# thermocouple_1.net
KiCad netlist of a schematic drawn in Altium Designer
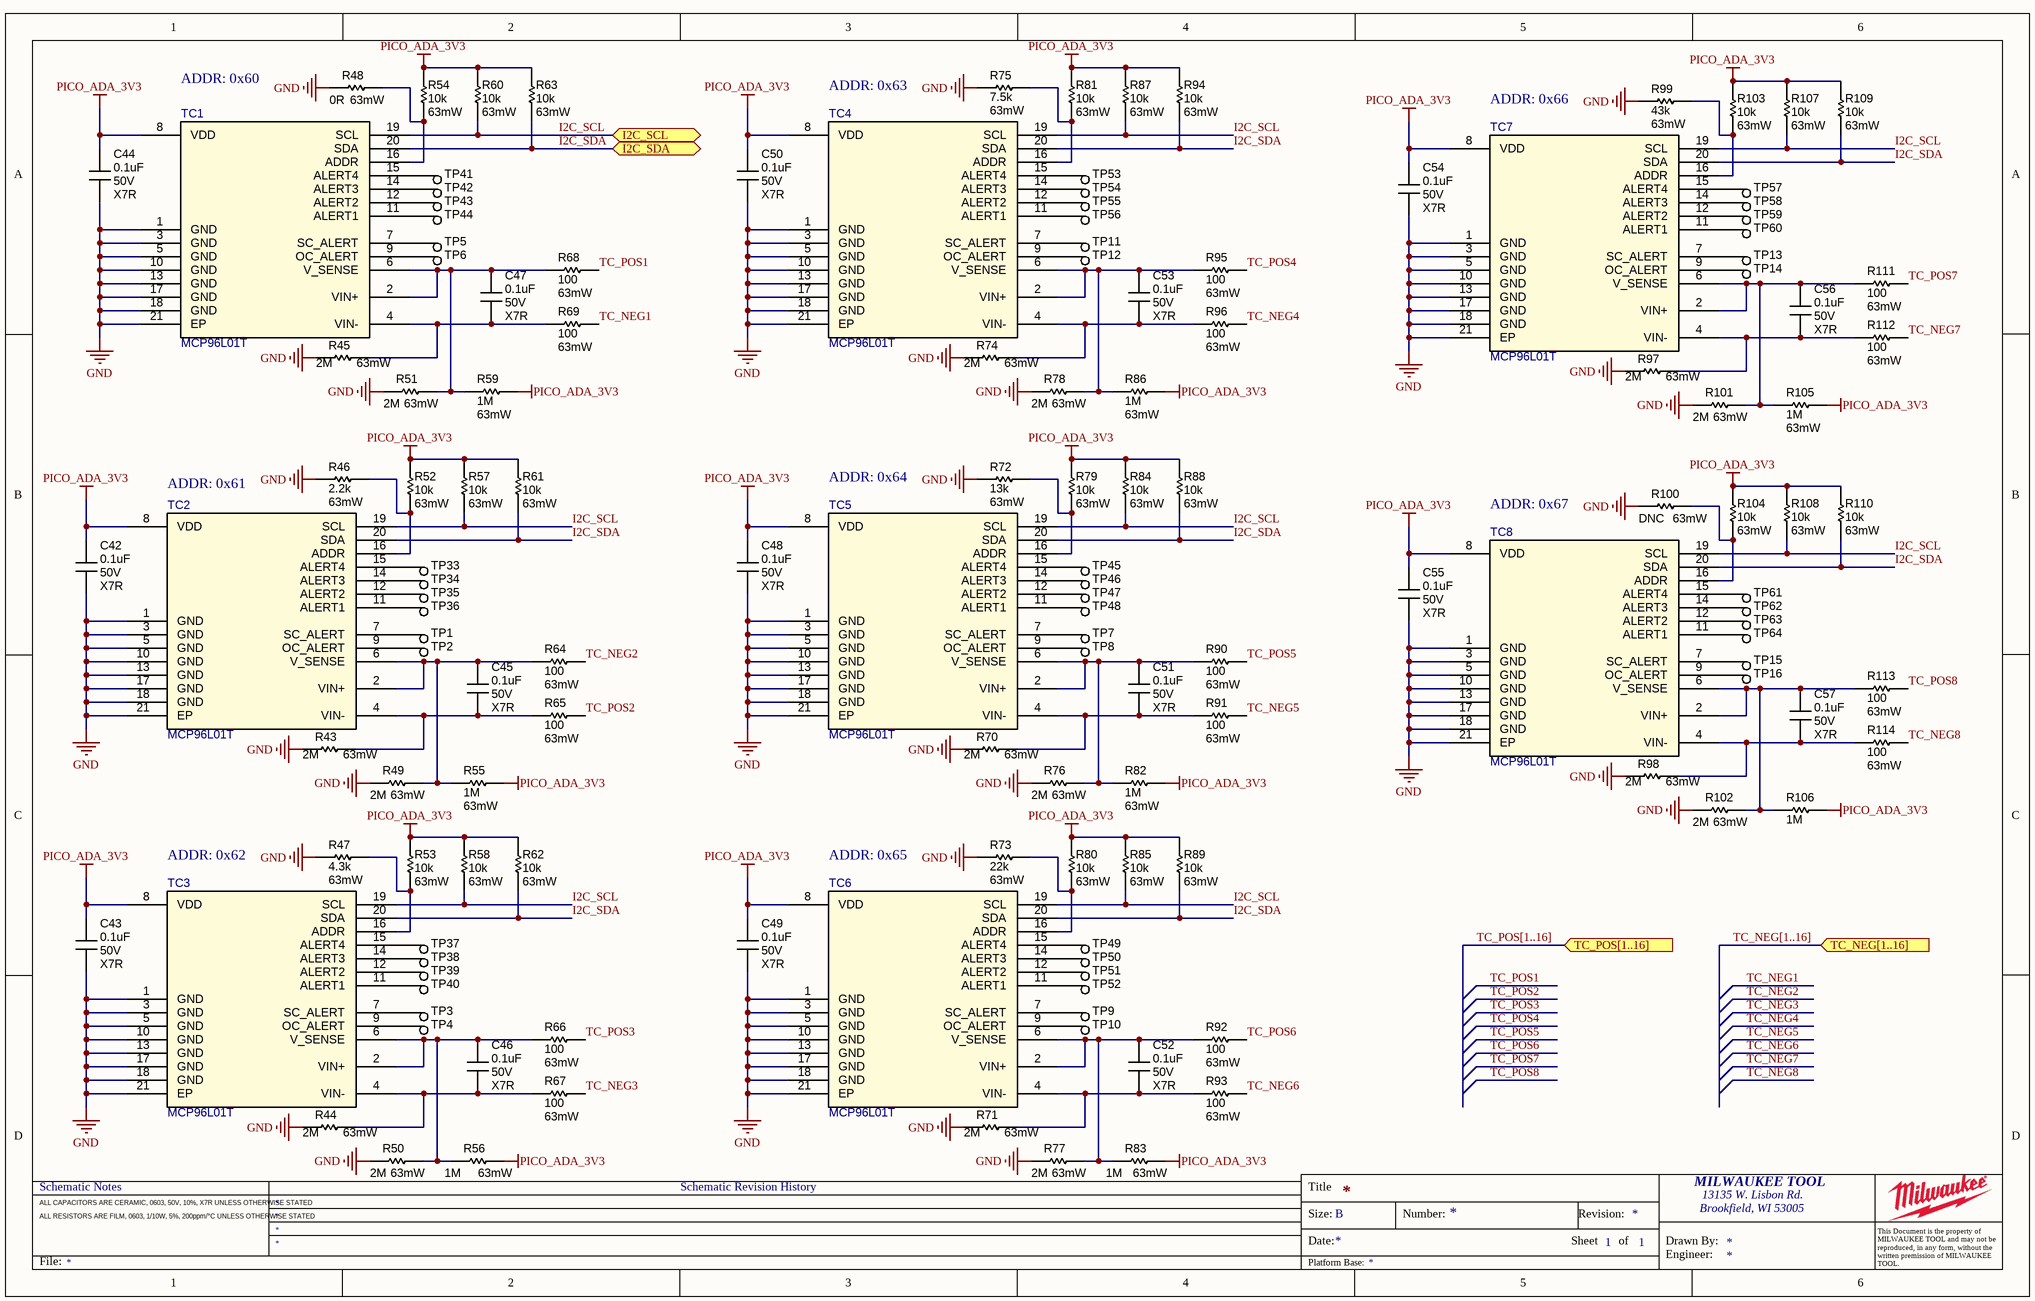
[diagram p0: thermocouple_1.SchDoc]

(export (version "E")
  (design (tool "Eeschema 10.0.6"))
  (components
    (comp (ref "C42")
      (value "0.1uF")
      (footprint "CAPC1608X09N")
      (description "CAP CER 0.1UF 50V X7R 0603")
      (fields
        (field (name "TOLERANCE") "10%")
        (field (name "MFR") "KEMET")
        (field (name "VOLTAGE RATING") "50V")
        (field (name "TEMP COEFF") "X7R")
      )
      (libsource (lib "General_Library") (part "CMP-004-0070"))
    )
    (comp (ref "C43")
      (value "0.1uF")
      (footprint "CAPC1608X09N")
      (description "CAP CER 0.1UF 50V X7R 0603")
      (fields
        (field (name "TOLERANCE") "10%")
        (field (name "MFR") "KEMET")
        (field (name "VOLTAGE RATING") "50V")
        (field (name "TEMP COEFF") "X7R")
      )
      (libsource (lib "General_Library") (part "CMP-004-0070"))
    )
    (comp (ref "C44")
      (value "0.1uF")
      (footprint "CAPC1608X09N")
      (description "CAP CER 0.1UF 50V X7R 0603")
      (fields
        (field (name "TOLERANCE") "10%")
        (field (name "MFR") "KEMET")
        (field (name "VOLTAGE RATING") "50V")
        (field (name "TEMP COEFF") "X7R")
      )
      (libsource (lib "General_Library") (part "CMP-004-0070"))
    )
    (comp (ref "C45")
      (value "0.1uF")
      (footprint "CAPC1005X06N")
      (description "CAP CER SMD 0.1UF 50V X7R 0402")
      (fields
        (field (name "TOLERANCE") "10%")
        (field (name "MFR") "Murata Electronics")
        (field (name "VOLTAGE RATING") "50V")
        (field (name "TEMP COEFF") "X7R")
      )
      (libsource (lib "General_Library") (part "CMP-004-0076"))
    )
    (comp (ref "C46")
      (value "0.1uF")
      (footprint "CAPC1005X06N")
      (description "CAP CER SMD 0.1UF 50V X7R 0402")
      (fields
        (field (name "TOLERANCE") "10%")
        (field (name "MFR") "Murata Electronics")
        (field (name "VOLTAGE RATING") "50V")
        (field (name "TEMP COEFF") "X7R")
      )
      (libsource (lib "General_Library") (part "CMP-004-0076"))
    )
    (comp (ref "C47")
      (value "0.1uF")
      (footprint "CAPC1005X06N")
      (description "CAP CER SMD 0.1UF 50V X7R 0402")
      (fields
        (field (name "TOLERANCE") "10%")
        (field (name "MFR") "Murata Electronics")
        (field (name "VOLTAGE RATING") "50V")
        (field (name "TEMP COEFF") "X7R")
      )
      (libsource (lib "General_Library") (part "CMP-004-0076"))
    )
    (comp (ref "C48")
      (value "0.1uF")
      (footprint "CAPC1608X09N")
      (description "CAP CER 0.1UF 50V X7R 0603")
      (fields
        (field (name "TOLERANCE") "10%")
        (field (name "MFR") "KEMET")
        (field (name "VOLTAGE RATING") "50V")
        (field (name "TEMP COEFF") "X7R")
      )
      (libsource (lib "General_Library") (part "CMP-004-0070"))
    )
    (comp (ref "C49")
      (value "0.1uF")
      (footprint "CAPC1608X09N")
      (description "CAP CER 0.1UF 50V X7R 0603")
      (fields
        (field (name "TOLERANCE") "10%")
        (field (name "MFR") "KEMET")
        (field (name "VOLTAGE RATING") "50V")
        (field (name "TEMP COEFF") "X7R")
      )
      (libsource (lib "General_Library") (part "CMP-004-0070"))
    )
    (comp (ref "C50")
      (value "0.1uF")
      (footprint "CAPC1608X09N")
      (description "CAP CER 0.1UF 50V X7R 0603")
      (fields
        (field (name "TOLERANCE") "10%")
        (field (name "MFR") "KEMET")
        (field (name "VOLTAGE RATING") "50V")
        (field (name "TEMP COEFF") "X7R")
      )
      (libsource (lib "General_Library") (part "CMP-004-0070"))
    )
    (comp (ref "C51")
      (value "0.1uF")
      (footprint "CAPC1005X06N")
      (description "CAP CER SMD 0.1UF 50V X7R 0402")
      (fields
        (field (name "TOLERANCE") "10%")
        (field (name "MFR") "Murata Electronics")
        (field (name "VOLTAGE RATING") "50V")
        (field (name "TEMP COEFF") "X7R")
      )
      (libsource (lib "General_Library") (part "CMP-004-0076"))
    )
    (comp (ref "C52")
      (value "0.1uF")
      (footprint "CAPC1005X06N")
      (description "CAP CER SMD 0.1UF 50V X7R 0402")
      (fields
        (field (name "TOLERANCE") "10%")
        (field (name "MFR") "Murata Electronics")
        (field (name "VOLTAGE RATING") "50V")
        (field (name "TEMP COEFF") "X7R")
      )
      (libsource (lib "General_Library") (part "CMP-004-0076"))
    )
    (comp (ref "C53")
      (value "0.1uF")
      (footprint "CAPC1005X06N")
      (description "CAP CER SMD 0.1UF 50V X7R 0402")
      (fields
        (field (name "TOLERANCE") "10%")
        (field (name "MFR") "Murata Electronics")
        (field (name "VOLTAGE RATING") "50V")
        (field (name "TEMP COEFF") "X7R")
      )
      (libsource (lib "General_Library") (part "CMP-004-0076"))
    )
    (comp (ref "C54")
      (value "0.1uF")
      (footprint "CAPC1608X09N")
      (description "CAP CER 0.1UF 50V X7R 0603")
      (fields
        (field (name "TOLERANCE") "10%")
        (field (name "MFR") "KEMET")
        (field (name "VOLTAGE RATING") "50V")
        (field (name "TEMP COEFF") "X7R")
      )
      (libsource (lib "General_Library") (part "CMP-004-0070"))
    )
    (comp (ref "C55")
      (value "0.1uF")
      (footprint "CAPC1608X09N")
      (description "CAP CER 0.1UF 50V X7R 0603")
      (fields
        (field (name "TOLERANCE") "10%")
        (field (name "MFR") "KEMET")
        (field (name "VOLTAGE RATING") "50V")
        (field (name "TEMP COEFF") "X7R")
      )
      (libsource (lib "General_Library") (part "CMP-004-0070"))
    )
    (comp (ref "C56")
      (value "0.1uF")
      (footprint "CAPC1005X06N")
      (description "CAP CER SMD 0.1UF 50V X7R 0402")
      (fields
        (field (name "TOLERANCE") "10%")
        (field (name "MFR") "Murata Electronics")
        (field (name "VOLTAGE RATING") "50V")
        (field (name "TEMP COEFF") "X7R")
      )
      (libsource (lib "General_Library") (part "CMP-004-0076"))
    )
    (comp (ref "C57")
      (value "0.1uF")
      (footprint "CAPC1005X06N")
      (description "CAP CER SMD 0.1UF 50V X7R 0402")
      (fields
        (field (name "TOLERANCE") "10%")
        (field (name "MFR") "Murata Electronics")
        (field (name "VOLTAGE RATING") "50V")
        (field (name "TEMP COEFF") "X7R")
      )
      (libsource (lib "General_Library") (part "CMP-004-0076"))
    )
    (comp (ref "R43")
      (value "2M")
      (footprint "RESC1005X04N")
      (description "RES SMD 2M OHM 1% 1/16W 0402")
      (fields (field (name "TOLERANCE") "1%") (field (name "MFR") "YAGEO") (field (name "WATTAGE") "63mW"))
      (libsource (lib "General_Library") (part "CMP-025-0172"))
    )
    (comp (ref "R44")
      (value "2M")
      (footprint "RESC1005X04N")
      (description "RES SMD 2M OHM 1% 1/16W 0402")
      (fields (field (name "TOLERANCE") "1%") (field (name "MFR") "YAGEO") (field (name "WATTAGE") "63mW"))
      (libsource (lib "General_Library") (part "CMP-025-0172"))
    )
    (comp (ref "R45")
      (value "2M")
      (footprint "RESC1005X04N")
      (description "RES SMD 2M OHM 1% 1/16W 0402")
      (fields (field (name "TOLERANCE") "1%") (field (name "MFR") "YAGEO") (field (name "WATTAGE") "63mW"))
      (libsource (lib "General_Library") (part "CMP-025-0172"))
    )
    (comp (ref "R46")
      (value "2.2k")
      (footprint "RESC1005X04N")
      (description "RES SMD 2.2K OHM 1% 1/16W 0402")
      (fields (field (name "TOLERANCE") "1%") (field (name "MFR") "YAGEO") (field (name "WATTAGE") "63mW"))
      (libsource (lib "General_Library") (part "CMP-025-0171"))
    )
    (comp (ref "R47")
      (value "4.3k")
      (footprint "RESC1005X04N")
      (description "RES SMD 4.3K OHM 1% 1/16W 0402")
      (fields (field (name "TOLERANCE") "1%") (field (name "MFR") "Yageo") (field (name "WATTAGE") "63mW"))
      (libsource (lib "General_Library") (part "CMP-025-0176"))
    )
    (comp (ref "R48")
      (value "0R")
      (footprint "RESC1005X04N")
      (description "RES SMD 0 OHM JUMPER 1/16W 0402")
      (fields
        (field (name "MFR") "Stackpole Electronics Inc")
        (field (name "TOLERANCE") "Jumper")
        (field (name "WATTAGE") "63mW")
      )
      (libsource (lib "General_Library") (part "CMP-025-0102"))
    )
    (comp (ref "R49")
      (value "2M")
      (footprint "RESC1005X04N")
      (description "RES SMD 2M OHM 1% 1/16W 0402")
      (fields (field (name "TOLERANCE") "1%") (field (name "MFR") "YAGEO") (field (name "WATTAGE") "63mW"))
      (libsource (lib "General_Library") (part "CMP-025-0172"))
    )
    (comp (ref "R50")
      (value "2M")
      (footprint "RESC1005X04N")
      (description "RES SMD 2M OHM 1% 1/16W 0402")
      (fields (field (name "TOLERANCE") "1%") (field (name "MFR") "YAGEO") (field (name "WATTAGE") "63mW"))
      (libsource (lib "General_Library") (part "CMP-025-0172"))
    )
    (comp (ref "R51")
      (value "2M")
      (footprint "RESC1005X04N")
      (description "RES SMD 2M OHM 1% 1/16W 0402")
      (fields (field (name "TOLERANCE") "1%") (field (name "MFR") "YAGEO") (field (name "WATTAGE") "63mW"))
      (libsource (lib "General_Library") (part "CMP-025-0172"))
    )
    (comp (ref "R52")
      (value "10k")
      (footprint "RESC1005X04N")
      (description "RES SMD 10K OHM 0.5% 1/16W 0402")
      (fields
        (field (name "MFR") "Panasonic Electronic Components")
        (field (name "TOLERANCE") "0.5%")
        (field (name "WATTAGE") "63mW")
      )
      (libsource (lib "Schlib1") (part "CMP-025-0026"))
    )
    (comp (ref "R53")
      (value "10k")
      (footprint "RESC1005X04N")
      (description "RES SMD 10K OHM 0.5% 1/16W 0402")
      (fields
        (field (name "MFR") "Panasonic Electronic Components")
        (field (name "TOLERANCE") "0.5%")
        (field (name "WATTAGE") "63mW")
      )
      (libsource (lib "Schlib1") (part "CMP-025-0026"))
    )
    (comp (ref "R54")
      (value "10k")
      (footprint "RESC1005X04N")
      (description "RES SMD 10K OHM 0.5% 1/16W 0402")
      (fields
        (field (name "MFR") "Panasonic Electronic Components")
        (field (name "TOLERANCE") "0.5%")
        (field (name "WATTAGE") "63mW")
      )
      (libsource (lib "Schlib1") (part "CMP-025-0026"))
    )
    (comp (ref "R55")
      (value "1M")
      (footprint "RESC1005X04N")
      (description "RES SMD 1M OHM 1% 1/16W 0402")
      (fields (field (name "TOLERANCE") "1%") (field (name "MFR") "YAGEO") (field (name "WATTAGE") "63mW"))
      (libsource (lib "General_Library") (part "CMP-025-0173"))
    )
    (comp (ref "R56")
      (value "1M")
      (footprint "RESC1005X04N")
      (description "RES SMD 1M OHM 1% 1/16W 0402")
      (fields (field (name "TOLERANCE") "1%") (field (name "MFR") "YAGEO") (field (name "WATTAGE") "63mW"))
      (libsource (lib "General_Library") (part "CMP-025-0173"))
    )
    (comp (ref "R57")
      (value "10k")
      (footprint "RESC1005X04N")
      (description "RES SMD 10K OHM 0.5% 1/16W 0402")
      (fields
        (field (name "MFR") "Panasonic Electronic Components")
        (field (name "TOLERANCE") "0.5%")
        (field (name "WATTAGE") "63mW")
      )
      (libsource (lib "Schlib1") (part "CMP-025-0026"))
    )
    (comp (ref "R58")
      (value "10k")
      (footprint "RESC1005X04N")
      (description "RES SMD 10K OHM 0.5% 1/16W 0402")
      (fields
        (field (name "MFR") "Panasonic Electronic Components")
        (field (name "TOLERANCE") "0.5%")
        (field (name "WATTAGE") "63mW")
      )
      (libsource (lib "Schlib1") (part "CMP-025-0026"))
    )
    (comp (ref "R59")
      (value "1M")
      (footprint "RESC1005X04N")
      (description "RES SMD 1M OHM 1% 1/16W 0402")
      (fields (field (name "TOLERANCE") "1%") (field (name "MFR") "YAGEO") (field (name "WATTAGE") "63mW"))
      (libsource (lib "General_Library") (part "CMP-025-0173"))
    )
    (comp (ref "R60")
      (value "10k")
      (footprint "RESC1005X04N")
      (description "RES SMD 10K OHM 0.5% 1/16W 0402")
      (fields
        (field (name "MFR") "Panasonic Electronic Components")
        (field (name "TOLERANCE") "0.5%")
        (field (name "WATTAGE") "63mW")
      )
      (libsource (lib "Schlib1") (part "CMP-025-0026"))
    )
    (comp (ref "R61")
      (value "10k")
      (footprint "RESC1005X04N")
      (description "RES SMD 10K OHM 0.5% 1/16W 0402")
      (fields
        (field (name "MFR") "Panasonic Electronic Components")
        (field (name "TOLERANCE") "0.5%")
        (field (name "WATTAGE") "63mW")
      )
      (libsource (lib "Schlib1") (part "CMP-025-0026"))
    )
    (comp (ref "R62")
      (value "10k")
      (footprint "RESC1005X04N")
      (description "RES SMD 10K OHM 0.5% 1/16W 0402")
      (fields
        (field (name "MFR") "Panasonic Electronic Components")
        (field (name "TOLERANCE") "0.5%")
        (field (name "WATTAGE") "63mW")
      )
      (libsource (lib "Schlib1") (part "CMP-025-0026"))
    )
    (comp (ref "R63")
      (value "10k")
      (footprint "RESC1005X04N")
      (description "RES SMD 10K OHM 0.5% 1/16W 0402")
      (fields
        (field (name "MFR") "Panasonic Electronic Components")
        (field (name "TOLERANCE") "0.5%")
        (field (name "WATTAGE") "63mW")
      )
      (libsource (lib "Schlib1") (part "CMP-025-0026"))
    )
    (comp (ref "R64")
      (value "100")
      (footprint "RESC1005X04N")
      (description "RES SMD 100 OHM 1% 1/16W 0402")
      (fields
        (field (name "TOLERANCE") "1%")
        (field (name "MFR") "Stackpole Electronics Inc")
        (field (name "WATTAGE") "63mW")
      )
      (libsource (lib "General_Library") (part "CMP-025-0156"))
    )
    (comp (ref "R65")
      (value "100")
      (footprint "RESC1005X04N")
      (description "RES SMD 100 OHM 1% 1/16W 0402")
      (fields
        (field (name "TOLERANCE") "1%")
        (field (name "MFR") "Stackpole Electronics Inc")
        (field (name "WATTAGE") "63mW")
      )
      (libsource (lib "General_Library") (part "CMP-025-0156"))
    )
    (comp (ref "R66")
      (value "100")
      (footprint "RESC1005X04N")
      (description "RES SMD 100 OHM 1% 1/16W 0402")
      (fields
        (field (name "TOLERANCE") "1%")
        (field (name "MFR") "Stackpole Electronics Inc")
        (field (name "WATTAGE") "63mW")
      )
      (libsource (lib "General_Library") (part "CMP-025-0156"))
    )
    (comp (ref "R67")
      (value "100")
      (footprint "RESC1005X04N")
      (description "RES SMD 100 OHM 1% 1/16W 0402")
      (fields
        (field (name "TOLERANCE") "1%")
        (field (name "MFR") "Stackpole Electronics Inc")
        (field (name "WATTAGE") "63mW")
      )
      (libsource (lib "General_Library") (part "CMP-025-0156"))
    )
    (comp (ref "R68")
      (value "100")
      (footprint "RESC1005X04N")
      (description "RES SMD 100 OHM 1% 1/16W 0402")
      (fields
        (field (name "TOLERANCE") "1%")
        (field (name "MFR") "Stackpole Electronics Inc")
        (field (name "WATTAGE") "63mW")
      )
      (libsource (lib "General_Library") (part "CMP-025-0156"))
    )
    (comp (ref "R69")
      (value "100")
      (footprint "RESC1005X04N")
      (description "RES SMD 100 OHM 1% 1/16W 0402")
      (fields
        (field (name "TOLERANCE") "1%")
        (field (name "MFR") "Stackpole Electronics Inc")
        (field (name "WATTAGE") "63mW")
      )
      (libsource (lib "General_Library") (part "CMP-025-0156"))
    )
    (comp (ref "R70")
      (value "2M")
      (footprint "RESC1005X04N")
      (description "RES SMD 2M OHM 1% 1/16W 0402")
      (fields (field (name "TOLERANCE") "1%") (field (name "MFR") "YAGEO") (field (name "WATTAGE") "63mW"))
      (libsource (lib "General_Library") (part "CMP-025-0172"))
    )
    (comp (ref "R71")
      (value "2M")
      (footprint "RESC1005X04N")
      (description "RES SMD 2M OHM 1% 1/16W 0402")
      (fields (field (name "TOLERANCE") "1%") (field (name "MFR") "YAGEO") (field (name "WATTAGE") "63mW"))
      (libsource (lib "General_Library") (part "CMP-025-0172"))
    )
    (comp (ref "R72")
      (value "13k")
      (footprint "RESC1005X04N")
      (description "RES SMD 13K OHM 1% 1/16W 0402")
      (fields (field (name "TOLERANCE") "1%") (field (name "MFR") "Yageo") (field (name "WATTAGE") "63mW"))
      (libsource (lib "General_Library") (part "CMP-025-0178"))
    )
    (comp (ref "R73")
      (value "22k")
      (footprint "RESC1005X04N")
      (description "RES SMD 22K OHM 1% 1/16W 0402")
      (fields (field (name "TOLERANCE") "1%") (field (name "MFR") "Yageo") (field (name "WATTAGE") "63mW"))
      (libsource (lib "General_Library") (part "CMP-025-0179"))
    )
    (comp (ref "R74")
      (value "2M")
      (footprint "RESC1005X04N")
      (description "RES SMD 2M OHM 1% 1/16W 0402")
      (fields (field (name "TOLERANCE") "1%") (field (name "MFR") "YAGEO") (field (name "WATTAGE") "63mW"))
      (libsource (lib "General_Library") (part "CMP-025-0172"))
    )
    (comp (ref "R75")
      (value "7.5k")
      (footprint "RESC1005X04N")
      (description "RES SMD 7.5K OHM 1% 1/16W 0402")
      (fields (field (name "TOLERANCE") "1%") (field (name "MFR") "Yageo") (field (name "WATTAGE") "63mW"))
      (libsource (lib "General_Library") (part "CMP-025-0177"))
    )
    (comp (ref "R76")
      (value "2M")
      (footprint "RESC1005X04N")
      (description "RES SMD 2M OHM 1% 1/16W 0402")
      (fields (field (name "TOLERANCE") "1%") (field (name "MFR") "YAGEO") (field (name "WATTAGE") "63mW"))
      (libsource (lib "General_Library") (part "CMP-025-0172"))
    )
    (comp (ref "R77")
      (value "2M")
      (footprint "RESC1005X04N")
      (description "RES SMD 2M OHM 1% 1/16W 0402")
      (fields (field (name "TOLERANCE") "1%") (field (name "MFR") "YAGEO") (field (name "WATTAGE") "63mW"))
      (libsource (lib "General_Library") (part "CMP-025-0172"))
    )
    (comp (ref "R78")
      (value "2M")
      (footprint "RESC1005X04N")
      (description "RES SMD 2M OHM 1% 1/16W 0402")
      (fields (field (name "TOLERANCE") "1%") (field (name "MFR") "YAGEO") (field (name "WATTAGE") "63mW"))
      (libsource (lib "General_Library") (part "CMP-025-0172"))
    )
    (comp (ref "R79")
      (value "10k")
      (footprint "RESC1005X04N")
      (description "RES SMD 10K OHM 0.5% 1/16W 0402")
      (fields
        (field (name "MFR") "Panasonic Electronic Components")
        (field (name "TOLERANCE") "0.5%")
        (field (name "WATTAGE") "63mW")
      )
      (libsource (lib "Schlib1") (part "CMP-025-0026"))
    )
    (comp (ref "R80")
      (value "10k")
      (footprint "RESC1005X04N")
      (description "RES SMD 10K OHM 0.5% 1/16W 0402")
      (fields
        (field (name "MFR") "Panasonic Electronic Components")
        (field (name "TOLERANCE") "0.5%")
        (field (name "WATTAGE") "63mW")
      )
      (libsource (lib "Schlib1") (part "CMP-025-0026"))
    )
    (comp (ref "R81")
      (value "10k")
      (footprint "RESC1005X04N")
      (description "RES SMD 10K OHM 0.5% 1/16W 0402")
      (fields
        (field (name "MFR") "Panasonic Electronic Components")
        (field (name "TOLERANCE") "0.5%")
        (field (name "WATTAGE") "63mW")
      )
      (libsource (lib "Schlib1") (part "CMP-025-0026"))
    )
    (comp (ref "R82")
      (value "1M")
      (footprint "RESC1005X04N")
      (description "RES SMD 1M OHM 1% 1/16W 0402")
      (fields (field (name "TOLERANCE") "1%") (field (name "MFR") "YAGEO") (field (name "WATTAGE") "63mW"))
      (libsource (lib "General_Library") (part "CMP-025-0173"))
    )
    (comp (ref "R83")
      (value "1M")
      (footprint "RESC1005X04N")
      (description "RES SMD 1M OHM 1% 1/16W 0402")
      (fields (field (name "TOLERANCE") "1%") (field (name "MFR") "YAGEO") (field (name "WATTAGE") "63mW"))
      (libsource (lib "General_Library") (part "CMP-025-0173"))
    )
    (comp (ref "R84")
      (value "10k")
      (footprint "RESC1005X04N")
      (description "RES SMD 10K OHM 0.5% 1/16W 0402")
      (fields
        (field (name "MFR") "Panasonic Electronic Components")
        (field (name "TOLERANCE") "0.5%")
        (field (name "WATTAGE") "63mW")
      )
      (libsource (lib "Schlib1") (part "CMP-025-0026"))
    )
    (comp (ref "R85")
      (value "10k")
      (footprint "RESC1005X04N")
      (description "RES SMD 10K OHM 0.5% 1/16W 0402")
      (fields
        (field (name "MFR") "Panasonic Electronic Components")
        (field (name "TOLERANCE") "0.5%")
        (field (name "WATTAGE") "63mW")
      )
      (libsource (lib "Schlib1") (part "CMP-025-0026"))
    )
    (comp (ref "R86")
      (value "1M")
      (footprint "RESC1005X04N")
      (description "RES SMD 1M OHM 1% 1/16W 0402")
      (fields (field (name "TOLERANCE") "1%") (field (name "MFR") "YAGEO") (field (name "WATTAGE") "63mW"))
      (libsource (lib "General_Library") (part "CMP-025-0173"))
    )
    (comp (ref "R87")
      (value "10k")
      (footprint "RESC1005X04N")
      (description "RES SMD 10K OHM 0.5% 1/16W 0402")
      (fields
        (field (name "MFR") "Panasonic Electronic Components")
        (field (name "TOLERANCE") "0.5%")
        (field (name "WATTAGE") "63mW")
      )
      (libsource (lib "Schlib1") (part "CMP-025-0026"))
    )
    (comp (ref "R88")
      (value "10k")
      (footprint "RESC1005X04N")
      (description "RES SMD 10K OHM 0.5% 1/16W 0402")
      (fields
        (field (name "MFR") "Panasonic Electronic Components")
        (field (name "TOLERANCE") "0.5%")
        (field (name "WATTAGE") "63mW")
      )
      (libsource (lib "Schlib1") (part "CMP-025-0026"))
    )
    (comp (ref "R89")
      (value "10k")
      (footprint "RESC1005X04N")
      (description "RES SMD 10K OHM 0.5% 1/16W 0402")
      (fields
        (field (name "MFR") "Panasonic Electronic Components")
        (field (name "TOLERANCE") "0.5%")
        (field (name "WATTAGE") "63mW")
      )
      (libsource (lib "Schlib1") (part "CMP-025-0026"))
    )
    (comp (ref "R90")
      (value "100")
      (footprint "RESC1005X04N")
      (description "RES SMD 100 OHM 1% 1/16W 0402")
      (fields
        (field (name "TOLERANCE") "1%")
        (field (name "MFR") "Stackpole Electronics Inc")
        (field (name "WATTAGE") "63mW")
      )
      (libsource (lib "General_Library") (part "CMP-025-0156"))
    )
    (comp (ref "R91")
      (value "100")
      (footprint "RESC1005X04N")
      (description "RES SMD 100 OHM 1% 1/16W 0402")
      (fields
        (field (name "TOLERANCE") "1%")
        (field (name "MFR") "Stackpole Electronics Inc")
        (field (name "WATTAGE") "63mW")
      )
      (libsource (lib "General_Library") (part "CMP-025-0156"))
    )
    (comp (ref "R92")
      (value "100")
      (footprint "RESC1005X04N")
      (description "RES SMD 100 OHM 1% 1/16W 0402")
      (fields
        (field (name "TOLERANCE") "1%")
        (field (name "MFR") "Stackpole Electronics Inc")
        (field (name "WATTAGE") "63mW")
      )
      (libsource (lib "General_Library") (part "CMP-025-0156"))
    )
    (comp (ref "R93")
      (value "100")
      (footprint "RESC1005X04N")
      (description "RES SMD 100 OHM 1% 1/16W 0402")
      (fields
        (field (name "TOLERANCE") "1%")
        (field (name "MFR") "Stackpole Electronics Inc")
        (field (name "WATTAGE") "63mW")
      )
      (libsource (lib "General_Library") (part "CMP-025-0156"))
    )
    (comp (ref "R94")
      (value "10k")
      (footprint "RESC1005X04N")
      (description "RES SMD 10K OHM 0.5% 1/16W 0402")
      (fields
        (field (name "MFR") "Panasonic Electronic Components")
        (field (name "TOLERANCE") "0.5%")
        (field (name "WATTAGE") "63mW")
      )
      (libsource (lib "Schlib1") (part "CMP-025-0026"))
    )
    (comp (ref "R95")
      (value "100")
      (footprint "RESC1005X04N")
      (description "RES SMD 100 OHM 1% 1/16W 0402")
      (fields
        (field (name "TOLERANCE") "1%")
        (field (name "MFR") "Stackpole Electronics Inc")
        (field (name "WATTAGE") "63mW")
      )
      (libsource (lib "General_Library") (part "CMP-025-0156"))
    )
    (comp (ref "R96")
      (value "100")
      (footprint "RESC1005X04N")
      (description "RES SMD 100 OHM 1% 1/16W 0402")
      (fields
        (field (name "TOLERANCE") "1%")
        (field (name "MFR") "Stackpole Electronics Inc")
        (field (name "WATTAGE") "63mW")
      )
      (libsource (lib "General_Library") (part "CMP-025-0156"))
    )
    (comp (ref "R97")
      (value "2M")
      (footprint "RESC1005X04N")
      (description "RES SMD 2M OHM 1% 1/16W 0402")
      (fields (field (name "TOLERANCE") "1%") (field (name "MFR") "YAGEO") (field (name "WATTAGE") "63mW"))
      (libsource (lib "General_Library") (part "CMP-025-0172"))
    )
    (comp (ref "R98")
      (value "2M")
      (footprint "RESC1005X04N")
      (description "RES SMD 2M OHM 1% 1/16W 0402")
      (fields (field (name "TOLERANCE") "1%") (field (name "MFR") "YAGEO") (field (name "WATTAGE") "63mW"))
      (libsource (lib "General_Library") (part "CMP-025-0172"))
    )
    (comp (ref "R99")
      (value "43k")
      (footprint "RESC1005X04N")
      (description "RES SMD 43K OHM 1% 1/16W 0402")
      (fields (field (name "TOLERANCE") "1%") (field (name "MFR") "Yageo") (field (name "WATTAGE") "63mW"))
      (libsource (lib "General_Library") (part "CMP-025-0180"))
    )
    (comp (ref "R100")
      (value "DNC")
      (footprint "RESC1005X04N")
      (description "RES SMD 0 OHM JUMPER 1/16W 0402")
      (fields
        (field (name "MFR") "Stackpole Electronics Inc")
        (field (name "TOLERANCE") "Jumper")
        (field (name "WATTAGE") "63mW")
      )
      (libsource (lib "General_Library") (part "CMP-025-0102"))
    )
    (comp (ref "R101")
      (value "2M")
      (footprint "RESC1005X04N")
      (description "RES SMD 2M OHM 1% 1/16W 0402")
      (fields (field (name "TOLERANCE") "1%") (field (name "MFR") "YAGEO") (field (name "WATTAGE") "63mW"))
      (libsource (lib "General_Library") (part "CMP-025-0172"))
    )
    (comp (ref "R102")
      (value "2M")
      (footprint "RESC1005X04N")
      (description "RES SMD 2M OHM 1% 1/16W 0402")
      (fields (field (name "TOLERANCE") "1%") (field (name "MFR") "YAGEO") (field (name "WATTAGE") "63mW"))
      (libsource (lib "General_Library") (part "CMP-025-0172"))
    )
    (comp (ref "R103")
      (value "10k")
      (footprint "RESC1005X04N")
      (description "RES SMD 10K OHM 0.5% 1/16W 0402")
      (fields
        (field (name "MFR") "Panasonic Electronic Components")
        (field (name "TOLERANCE") "0.5%")
        (field (name "WATTAGE") "63mW")
      )
      (libsource (lib "Schlib1") (part "CMP-025-0026"))
    )
    (comp (ref "R104")
      (value "10k")
      (footprint "RESC1005X04N")
      (description "RES SMD 10K OHM 0.5% 1/16W 0402")
      (fields
        (field (name "MFR") "Panasonic Electronic Components")
        (field (name "TOLERANCE") "0.5%")
        (field (name "WATTAGE") "63mW")
      )
      (libsource (lib "Schlib1") (part "CMP-025-0026"))
    )
    (comp (ref "R105")
      (value "1M")
      (footprint "RESC1005X04N")
      (description "RES SMD 1M OHM 1% 1/16W 0402")
      (fields (field (name "TOLERANCE") "1%") (field (name "MFR") "YAGEO") (field (name "WATTAGE") "63mW"))
      (libsource (lib "General_Library") (part "CMP-025-0173"))
    )
    (comp (ref "R106")
      (value "1M")
      (footprint "RESC1005X04N")
      (description "RES SMD 1M OHM 1% 1/16W 0402")
      (fields (field (name "TOLERANCE") "1%") (field (name "MFR") "YAGEO"))
      (libsource (lib "General_Library") (part "CMP-025-0173"))
    )
    (comp (ref "R107")
      (value "10k")
      (footprint "RESC1005X04N")
      (description "RES SMD 10K OHM 0.5% 1/16W 0402")
      (fields
        (field (name "MFR") "Panasonic Electronic Components")
        (field (name "TOLERANCE") "0.5%")
        (field (name "WATTAGE") "63mW")
      )
      (libsource (lib "Schlib1") (part "CMP-025-0026"))
    )
    (comp (ref "R108")
      (value "10k")
      (footprint "RESC1005X04N")
      (description "RES SMD 10K OHM 0.5% 1/16W 0402")
      (fields
        (field (name "MFR") "Panasonic Electronic Components")
        (field (name "TOLERANCE") "0.5%")
        (field (name "WATTAGE") "63mW")
      )
      (libsource (lib "Schlib1") (part "CMP-025-0026"))
    )
    (comp (ref "R109")
      (value "10k")
      (footprint "RESC1005X04N")
      (description "RES SMD 10K OHM 0.5% 1/16W 0402")
      (fields
        (field (name "MFR") "Panasonic Electronic Components")
        (field (name "TOLERANCE") "0.5%")
        (field (name "WATTAGE") "63mW")
      )
      (libsource (lib "Schlib1") (part "CMP-025-0026"))
    )
    (comp (ref "R110")
      (value "10k")
      (footprint "RESC1005X04N")
      (description "RES SMD 10K OHM 0.5% 1/16W 0402")
      (fields
        (field (name "MFR") "Panasonic Electronic Components")
        (field (name "TOLERANCE") "0.5%")
        (field (name "WATTAGE") "63mW")
      )
      (libsource (lib "Schlib1") (part "CMP-025-0026"))
    )
    (comp (ref "R111")
      (value "100")
      (footprint "RESC1005X04N")
      (description "RES SMD 100 OHM 1% 1/16W 0402")
      (fields
        (field (name "TOLERANCE") "1%")
        (field (name "MFR") "Stackpole Electronics Inc")
        (field (name "WATTAGE") "63mW")
      )
      (libsource (lib "General_Library") (part "CMP-025-0156"))
    )
    (comp (ref "R112")
      (value "100")
      (footprint "RESC1005X04N")
      (description "RES SMD 100 OHM 1% 1/16W 0402")
      (fields
        (field (name "TOLERANCE") "1%")
        (field (name "MFR") "Stackpole Electronics Inc")
        (field (name "WATTAGE") "63mW")
      )
      (libsource (lib "General_Library") (part "CMP-025-0156"))
    )
    (comp (ref "R113")
      (value "100")
      (footprint "RESC1005X04N")
      (description "RES SMD 100 OHM 1% 1/16W 0402")
      (fields
        (field (name "TOLERANCE") "1%")
        (field (name "MFR") "Stackpole Electronics Inc")
        (field (name "WATTAGE") "63mW")
      )
      (libsource (lib "General_Library") (part "CMP-025-0156"))
    )
    (comp (ref "R114")
      (value "100")
      (footprint "RESC1005X04N")
      (description "RES SMD 100 OHM 1% 1/16W 0402")
      (fields
        (field (name "TOLERANCE") "1%")
        (field (name "MFR") "Stackpole Electronics Inc")
        (field (name "WATTAGE") "63mW")
      )
      (libsource (lib "General_Library") (part "CMP-025-0156"))
    )
    (comp (ref "TC1")
      (value "MCP96L01T")
      (footprint "Footprints:QFN65P500X500X100_HS-21N")
      (description "IC THERMOCOUPLE AMPLIFIER I2C")
      (fields (field (name "MFR") "Microchip"))
      (libsource (lib "Symbols") (part "CMP-017-0115"))
    )
    (comp (ref "TC2")
      (value "MCP96L01T")
      (footprint "Footprints:QFN65P500X500X100_HS-21N")
      (description "IC THERMOCOUPLE AMPLIFIER I2C")
      (fields (field (name "MFR") "Microchip"))
      (libsource (lib "Symbols") (part "CMP-017-0115"))
    )
    (comp (ref "TC3")
      (value "MCP96L01T")
      (footprint "Footprints:QFN65P500X500X100_HS-21N")
      (description "IC THERMOCOUPLE AMPLIFIER I2C")
      (fields (field (name "MFR") "Microchip"))
      (libsource (lib "Symbols") (part "CMP-017-0115"))
    )
    (comp (ref "TC4")
      (value "MCP96L01T")
      (footprint "Footprints:QFN65P500X500X100_HS-21N")
      (description "IC THERMOCOUPLE AMPLIFIER I2C")
      (fields (field (name "MFR") "Microchip"))
      (libsource (lib "Symbols") (part "CMP-017-0115"))
    )
    (comp (ref "TC5")
      (value "MCP96L01T")
      (footprint "Footprints:QFN65P500X500X100_HS-21N")
      (description "IC THERMOCOUPLE AMPLIFIER I2C")
      (fields (field (name "MFR") "Microchip"))
      (libsource (lib "Symbols") (part "CMP-017-0115"))
    )
    (comp (ref "TC6")
      (value "MCP96L01T")
      (footprint "Footprints:QFN65P500X500X100_HS-21N")
      (description "IC THERMOCOUPLE AMPLIFIER I2C")
      (fields (field (name "MFR") "Microchip"))
      (libsource (lib "Symbols") (part "CMP-017-0115"))
    )
    (comp (ref "TC7")
      (value "MCP96L01T")
      (footprint "Footprints:QFN65P500X500X100_HS-21N")
      (description "IC THERMOCOUPLE AMPLIFIER I2C")
      (fields (field (name "MFR") "Microchip"))
      (libsource (lib "Symbols") (part "CMP-017-0115"))
    )
    (comp (ref "TC8")
      (value "MCP96L01T")
      (footprint "Footprints:QFN65P500X500X100_HS-21N")
      (description "IC THERMOCOUPLE AMPLIFIER I2C")
      (fields (field (name "MFR") "Microchip"))
      (libsource (lib "Symbols") (part "CMP-017-0115"))
    )
    (comp (ref "TP1")
      (value "TP_SMT_1MM_CIR")
      (footprint "TP_SMT_1.0MM_CIR")
      (description "TP SMT 1mm Circle")
      (libsource (lib "General_Library") (part "CMP-019-0006"))
    )
    (comp (ref "TP2")
      (value "TP_SMT_1MM_CIR")
      (footprint "TP_SMT_1.0MM_CIR")
      (description "TP SMT 1mm Circle")
      (libsource (lib "General_Library") (part "CMP-019-0006"))
    )
    (comp (ref "TP3")
      (value "TP_SMT_1MM_CIR")
      (footprint "TP_SMT_1.0MM_CIR")
      (description "TP SMT 1mm Circle")
      (libsource (lib "General_Library") (part "CMP-019-0006"))
    )
    (comp (ref "TP4")
      (value "TP_SMT_1MM_CIR")
      (footprint "TP_SMT_1.0MM_CIR")
      (description "TP SMT 1mm Circle")
      (libsource (lib "General_Library") (part "CMP-019-0006"))
    )
    (comp (ref "TP5")
      (value "TP_SMT_1MM_CIR")
      (footprint "TP_SMT_1.0MM_CIR")
      (description "TP SMT 1mm Circle")
      (libsource (lib "General_Library") (part "CMP-019-0006"))
    )
    (comp (ref "TP6")
      (value "TP_SMT_1MM_CIR")
      (footprint "TP_SMT_1.0MM_CIR")
      (description "TP SMT 1mm Circle")
      (libsource (lib "General_Library") (part "CMP-019-0006"))
    )
    (comp (ref "TP7")
      (value "TP_SMT_1MM_CIR")
      (footprint "TP_SMT_1.0MM_CIR")
      (description "TP SMT 1mm Circle")
      (libsource (lib "General_Library") (part "CMP-019-0006"))
    )
    (comp (ref "TP8")
      (value "TP_SMT_1MM_CIR")
      (footprint "TP_SMT_1.0MM_CIR")
      (description "TP SMT 1mm Circle")
      (libsource (lib "General_Library") (part "CMP-019-0006"))
    )
    (comp (ref "TP9")
      (value "TP_SMT_1MM_CIR")
      (footprint "TP_SMT_1.0MM_CIR")
      (description "TP SMT 1mm Circle")
      (libsource (lib "General_Library") (part "CMP-019-0006"))
    )
    (comp (ref "TP10")
      (value "TP_SMT_1MM_CIR")
      (footprint "TP_SMT_1.0MM_CIR")
      (description "TP SMT 1mm Circle")
      (libsource (lib "General_Library") (part "CMP-019-0006"))
    )
    (comp (ref "TP11")
      (value "TP_SMT_1MM_CIR")
      (footprint "TP_SMT_1.0MM_CIR")
      (description "TP SMT 1mm Circle")
      (libsource (lib "General_Library") (part "CMP-019-0006"))
    )
    (comp (ref "TP12")
      (value "TP_SMT_1MM_CIR")
      (footprint "TP_SMT_1.0MM_CIR")
      (description "TP SMT 1mm Circle")
      (libsource (lib "General_Library") (part "CMP-019-0006"))
    )
    (comp (ref "TP13")
      (value "TP_SMT_1MM_CIR")
      (footprint "TP_SMT_1.0MM_CIR")
      (description "TP SMT 1mm Circle")
      (libsource (lib "General_Library") (part "CMP-019-0006"))
    )
    (comp (ref "TP14")
      (value "TP_SMT_1MM_CIR")
      (footprint "TP_SMT_1.0MM_CIR")
      (description "TP SMT 1mm Circle")
      (libsource (lib "General_Library") (part "CMP-019-0006"))
    )
    (comp (ref "TP15")
      (value "TP_SMT_1MM_CIR")
      (footprint "TP_SMT_1.0MM_CIR")
      (description "TP SMT 1mm Circle")
      (libsource (lib "General_Library") (part "CMP-019-0006"))
    )
    (comp (ref "TP16")
      (value "TP_SMT_1MM_CIR")
      (footprint "TP_SMT_1.0MM_CIR")
      (description "TP SMT 1mm Circle")
      (libsource (lib "General_Library") (part "CMP-019-0006"))
    )
    (comp (ref "TP33")
      (value "TP_SMT_1MM_CIR")
      (footprint "TP_SMT_1.0MM_CIR")
      (description "TP SMT 1mm Circle")
      (libsource (lib "General_Library") (part "CMP-019-0006"))
    )
    (comp (ref "TP34")
      (value "TP_SMT_1MM_CIR")
      (footprint "TP_SMT_1.0MM_CIR")
      (description "TP SMT 1mm Circle")
      (libsource (lib "General_Library") (part "CMP-019-0006"))
    )
    (comp (ref "TP35")
      (value "TP_SMT_1MM_CIR")
      (footprint "TP_SMT_1.0MM_CIR")
      (description "TP SMT 1mm Circle")
      (libsource (lib "General_Library") (part "CMP-019-0006"))
    )
    (comp (ref "TP36")
      (value "TP_SMT_1MM_CIR")
      (footprint "TP_SMT_1.0MM_CIR")
      (description "TP SMT 1mm Circle")
      (libsource (lib "General_Library") (part "CMP-019-0006"))
    )
    (comp (ref "TP37")
      (value "TP_SMT_1MM_CIR")
      (footprint "TP_SMT_1.0MM_CIR")
      (description "TP SMT 1mm Circle")
      (libsource (lib "General_Library") (part "CMP-019-0006"))
    )
    (comp (ref "TP38")
      (value "TP_SMT_1MM_CIR")
      (footprint "TP_SMT_1.0MM_CIR")
      (description "TP SMT 1mm Circle")
      (libsource (lib "General_Library") (part "CMP-019-0006"))
    )
    (comp (ref "TP39")
      (value "TP_SMT_1MM_CIR")
      (footprint "TP_SMT_1.0MM_CIR")
      (description "TP SMT 1mm Circle")
      (libsource (lib "General_Library") (part "CMP-019-0006"))
    )
    (comp (ref "TP40")
      (value "TP_SMT_1MM_CIR")
      (footprint "TP_SMT_1.0MM_CIR")
      (description "TP SMT 1mm Circle")
      (libsource (lib "General_Library") (part "CMP-019-0006"))
    )
    (comp (ref "TP41")
      (value "TP_SMT_1MM_CIR")
      (footprint "TP_SMT_1.0MM_CIR")
      (description "TP SMT 1mm Circle")
      (libsource (lib "General_Library") (part "CMP-019-0006"))
    )
    (comp (ref "TP42")
      (value "TP_SMT_1MM_CIR")
      (footprint "TP_SMT_1.0MM_CIR")
      (description "TP SMT 1mm Circle")
      (libsource (lib "General_Library") (part "CMP-019-0006"))
    )
    (comp (ref "TP43")
      (value "TP_SMT_1MM_CIR")
      (footprint "TP_SMT_1.0MM_CIR")
      (description "TP SMT 1mm Circle")
      (libsource (lib "General_Library") (part "CMP-019-0006"))
    )
    (comp (ref "TP44")
      (value "TP_SMT_1MM_CIR")
      (footprint "TP_SMT_1.0MM_CIR")
      (description "TP SMT 1mm Circle")
      (libsource (lib "General_Library") (part "CMP-019-0006"))
    )
    (comp (ref "TP45")
      (value "TP_SMT_1MM_CIR")
      (footprint "TP_SMT_1.0MM_CIR")
      (description "TP SMT 1mm Circle")
      (libsource (lib "General_Library") (part "CMP-019-0006"))
    )
    (comp (ref "TP46")
      (value "TP_SMT_1MM_CIR")
      (footprint "TP_SMT_1.0MM_CIR")
      (description "TP SMT 1mm Circle")
      (libsource (lib "General_Library") (part "CMP-019-0006"))
    )
    (comp (ref "TP47")
      (value "TP_SMT_1MM_CIR")
      (footprint "TP_SMT_1.0MM_CIR")
      (description "TP SMT 1mm Circle")
      (libsource (lib "General_Library") (part "CMP-019-0006"))
    )
    (comp (ref "TP48")
      (value "TP_SMT_1MM_CIR")
      (footprint "TP_SMT_1.0MM_CIR")
      (description "TP SMT 1mm Circle")
      (libsource (lib "General_Library") (part "CMP-019-0006"))
    )
    (comp (ref "TP49")
      (value "TP_SMT_1MM_CIR")
      (footprint "TP_SMT_1.0MM_CIR")
      (description "TP SMT 1mm Circle")
      (libsource (lib "General_Library") (part "CMP-019-0006"))
    )
    (comp (ref "TP50")
      (value "TP_SMT_1MM_CIR")
      (footprint "TP_SMT_1.0MM_CIR")
      (description "TP SMT 1mm Circle")
      (libsource (lib "General_Library") (part "CMP-019-0006"))
    )
    (comp (ref "TP51")
      (value "TP_SMT_1MM_CIR")
      (footprint "TP_SMT_1.0MM_CIR")
      (description "TP SMT 1mm Circle")
      (libsource (lib "General_Library") (part "CMP-019-0006"))
    )
    (comp (ref "TP52")
      (value "TP_SMT_1MM_CIR")
      (footprint "TP_SMT_1.0MM_CIR")
      (description "TP SMT 1mm Circle")
      (libsource (lib "General_Library") (part "CMP-019-0006"))
    )
    (comp (ref "TP53")
      (value "TP_SMT_1MM_CIR")
      (footprint "TP_SMT_1.0MM_CIR")
      (description "TP SMT 1mm Circle")
      (libsource (lib "General_Library") (part "CMP-019-0006"))
    )
    (comp (ref "TP54")
      (value "TP_SMT_1MM_CIR")
      (footprint "TP_SMT_1.0MM_CIR")
      (description "TP SMT 1mm Circle")
      (libsource (lib "General_Library") (part "CMP-019-0006"))
    )
    (comp (ref "TP55")
      (value "TP_SMT_1MM_CIR")
      (footprint "TP_SMT_1.0MM_CIR")
      (description "TP SMT 1mm Circle")
      (libsource (lib "General_Library") (part "CMP-019-0006"))
    )
    (comp (ref "TP56")
      (value "TP_SMT_1MM_CIR")
      (footprint "TP_SMT_1.0MM_CIR")
      (description "TP SMT 1mm Circle")
      (libsource (lib "General_Library") (part "CMP-019-0006"))
    )
    (comp (ref "TP57")
      (value "TP_SMT_1MM_CIR")
      (footprint "TP_SMT_1.0MM_CIR")
      (description "TP SMT 1mm Circle")
      (libsource (lib "General_Library") (part "CMP-019-0006"))
    )
    (comp (ref "TP58")
      (value "TP_SMT_1MM_CIR")
      (footprint "TP_SMT_1.0MM_CIR")
      (description "TP SMT 1mm Circle")
      (libsource (lib "General_Library") (part "CMP-019-0006"))
    )
    (comp (ref "TP59")
      (value "TP_SMT_1MM_CIR")
      (footprint "TP_SMT_1.0MM_CIR")
      (description "TP SMT 1mm Circle")
      (libsource (lib "General_Library") (part "CMP-019-0006"))
    )
    (comp (ref "TP60")
      (value "TP_SMT_1MM_CIR")
      (footprint "TP_SMT_1.0MM_CIR")
      (description "TP SMT 1mm Circle")
      (libsource (lib "General_Library") (part "CMP-019-0006"))
    )
    (comp (ref "TP61")
      (value "TP_SMT_1MM_CIR")
      (footprint "TP_SMT_1.0MM_CIR")
      (description "TP SMT 1mm Circle")
      (libsource (lib "General_Library") (part "CMP-019-0006"))
    )
    (comp (ref "TP62")
      (value "TP_SMT_1MM_CIR")
      (footprint "TP_SMT_1.0MM_CIR")
      (description "TP SMT 1mm Circle")
      (libsource (lib "General_Library") (part "CMP-019-0006"))
    )
    (comp (ref "TP63")
      (value "TP_SMT_1MM_CIR")
      (footprint "TP_SMT_1.0MM_CIR")
      (description "TP SMT 1mm Circle")
      (libsource (lib "General_Library") (part "CMP-019-0006"))
    )
    (comp (ref "TP64")
      (value "TP_SMT_1MM_CIR")
      (footprint "TP_SMT_1.0MM_CIR")
      (description "TP SMT 1mm Circle")
      (libsource (lib "General_Library") (part "CMP-019-0006"))
    )
  )
  (nets
    (net (code "17") (name "/I2C_SCL") (class "Default")
      (node (ref "R107") (pin "1") (pinfunction "1_1") (pintype "passive"))
      (node (ref "R108") (pin "1") (pinfunction "1_1") (pintype "passive"))
      (node (ref "R57") (pin "1") (pinfunction "1_1") (pintype "passive"))
      (node (ref "R58") (pin "1") (pinfunction "1_1") (pintype "passive"))
      (node (ref "R60") (pin "1") (pinfunction "1_1") (pintype "passive"))
      (node (ref "R84") (pin "1") (pinfunction "1_1") (pintype "passive"))
      (node (ref "R85") (pin "1") (pinfunction "1_1") (pintype "passive"))
      (node (ref "R87") (pin "1") (pinfunction "1_1") (pintype "passive"))
      (node (ref "TC1") (pin "19") (pinfunction "SCL_19") (pintype "passive"))
      (node (ref "TC2") (pin "19") (pinfunction "SCL_19") (pintype "passive"))
      (node (ref "TC3") (pin "19") (pinfunction "SCL_19") (pintype "passive"))
      (node (ref "TC4") (pin "19") (pinfunction "SCL_19") (pintype "passive"))
      (node (ref "TC5") (pin "19") (pinfunction "SCL_19") (pintype "passive"))
      (node (ref "TC6") (pin "19") (pinfunction "SCL_19") (pintype "passive"))
      (node (ref "TC7") (pin "19") (pinfunction "SCL_19") (pintype "passive"))
      (node (ref "TC8") (pin "19") (pinfunction "SCL_19") (pintype "passive"))
    )
    (net (code "18") (name "/I2C_SDA") (class "Default")
      (node (ref "R109") (pin "1") (pinfunction "1_1") (pintype "passive"))
      (node (ref "R110") (pin "1") (pinfunction "1_1") (pintype "passive"))
      (node (ref "R61") (pin "1") (pinfunction "1_1") (pintype "passive"))
      (node (ref "R62") (pin "1") (pinfunction "1_1") (pintype "passive"))
      (node (ref "R63") (pin "1") (pinfunction "1_1") (pintype "passive"))
      (node (ref "R88") (pin "1") (pinfunction "1_1") (pintype "passive"))
      (node (ref "R89") (pin "1") (pinfunction "1_1") (pintype "passive"))
      (node (ref "R94") (pin "1") (pinfunction "1_1") (pintype "passive"))
      (node (ref "TC1") (pin "20") (pinfunction "SDA_20") (pintype "passive"))
      (node (ref "TC2") (pin "20") (pinfunction "SDA_20") (pintype "passive"))
      (node (ref "TC3") (pin "20") (pinfunction "SDA_20") (pintype "passive"))
      (node (ref "TC4") (pin "20") (pinfunction "SDA_20") (pintype "passive"))
      (node (ref "TC5") (pin "20") (pinfunction "SDA_20") (pintype "passive"))
      (node (ref "TC6") (pin "20") (pinfunction "SDA_20") (pintype "passive"))
      (node (ref "TC7") (pin "20") (pinfunction "SDA_20") (pintype "passive"))
      (node (ref "TC8") (pin "20") (pinfunction "SDA_20") (pintype "passive"))
    )
    (net (code "19") (name "/TC_NEG1") (class "Default")
      (node (ref "R69") (pin "2") (pinfunction "2_2") (pintype "passive"))
    )
    (net (code "20") (name "/TC_NEG2") (class "Default")
      (node (ref "R64") (pin "2") (pinfunction "2_2") (pintype "passive"))
    )
    (net (code "21") (name "/TC_NEG3") (class "Default")
      (node (ref "R67") (pin "2") (pinfunction "2_2") (pintype "passive"))
    )
    (net (code "22") (name "/TC_NEG4") (class "Default")
      (node (ref "R96") (pin "2") (pinfunction "2_2") (pintype "passive"))
    )
    (net (code "23") (name "/TC_NEG5") (class "Default")
      (node (ref "R91") (pin "2") (pinfunction "2_2") (pintype "passive"))
    )
    (net (code "24") (name "/TC_NEG6") (class "Default")
      (node (ref "R93") (pin "2") (pinfunction "2_2") (pintype "passive"))
    )
    (net (code "25") (name "/TC_NEG7") (class "Default")
      (node (ref "R112") (pin "2") (pinfunction "2_2") (pintype "passive"))
    )
    (net (code "26") (name "/TC_NEG8") (class "Default")
      (node (ref "R114") (pin "2") (pinfunction "2_2") (pintype "passive"))
    )
    (net (code "28") (name "/TC_POS1") (class "Default")
      (node (ref "R68") (pin "2") (pinfunction "2_2") (pintype "passive"))
    )
    (net (code "29") (name "/TC_POS2") (class "Default")
      (node (ref "R65") (pin "2") (pinfunction "2_2") (pintype "passive"))
    )
    (net (code "30") (name "/TC_POS3") (class "Default")
      (node (ref "R66") (pin "2") (pinfunction "2_2") (pintype "passive"))
    )
    (net (code "31") (name "/TC_POS4") (class "Default")
      (node (ref "R95") (pin "2") (pinfunction "2_2") (pintype "passive"))
    )
    (net (code "32") (name "/TC_POS5") (class "Default")
      (node (ref "R90") (pin "2") (pinfunction "2_2") (pintype "passive"))
    )
    (net (code "33") (name "/TC_POS6") (class "Default")
      (node (ref "R92") (pin "2") (pinfunction "2_2") (pintype "passive"))
    )
    (net (code "34") (name "/TC_POS7") (class "Default")
      (node (ref "R111") (pin "2") (pinfunction "2_2") (pintype "passive"))
    )
    (net (code "35") (name "/TC_POS8") (class "Default")
      (node (ref "R113") (pin "2") (pinfunction "2_2") (pintype "passive"))
    )
    (net (code "37") (name "GND") (class "Default")
      (node (ref "C42") (pin "2") (pinfunction "2_2") (pintype "passive"))
      (node (ref "C43") (pin "2") (pinfunction "2_2") (pintype "passive"))
      (node (ref "C44") (pin "2") (pinfunction "2_2") (pintype "passive"))
      (node (ref "C48") (pin "2") (pinfunction "2_2") (pintype "passive"))
      (node (ref "C49") (pin "2") (pinfunction "2_2") (pintype "passive"))
      (node (ref "C50") (pin "2") (pinfunction "2_2") (pintype "passive"))
      (node (ref "C54") (pin "2") (pinfunction "2_2") (pintype "passive"))
      (node (ref "C55") (pin "2") (pinfunction "2_2") (pintype "passive"))
      (node (ref "R100") (pin "1") (pinfunction "1_1") (pintype "passive"))
      (node (ref "R101") (pin "1") (pinfunction "1_1") (pintype "passive"))
      (node (ref "R102") (pin "1") (pinfunction "1_1") (pintype "passive"))
      (node (ref "R43") (pin "1") (pinfunction "1_1") (pintype "passive"))
      (node (ref "R44") (pin "1") (pinfunction "1_1") (pintype "passive"))
      (node (ref "R45") (pin "1") (pinfunction "1_1") (pintype "passive"))
      (node (ref "R46") (pin "1") (pinfunction "1_1") (pintype "passive"))
      (node (ref "R47") (pin "1") (pinfunction "1_1") (pintype "passive"))
      (node (ref "R48") (pin "1") (pinfunction "1_1") (pintype "passive"))
      (node (ref "R49") (pin "1") (pinfunction "1_1") (pintype "passive"))
      (node (ref "R50") (pin "1") (pinfunction "1_1") (pintype "passive"))
      (node (ref "R51") (pin "1") (pinfunction "1_1") (pintype "passive"))
      (node (ref "R70") (pin "1") (pinfunction "1_1") (pintype "passive"))
      (node (ref "R71") (pin "1") (pinfunction "1_1") (pintype "passive"))
      (node (ref "R72") (pin "1") (pinfunction "1_1") (pintype "passive"))
      (node (ref "R73") (pin "1") (pinfunction "1_1") (pintype "passive"))
      (node (ref "R74") (pin "1") (pinfunction "1_1") (pintype "passive"))
      (node (ref "R75") (pin "1") (pinfunction "1_1") (pintype "passive"))
      (node (ref "R76") (pin "1") (pinfunction "1_1") (pintype "passive"))
      (node (ref "R77") (pin "1") (pinfunction "1_1") (pintype "passive"))
      (node (ref "R78") (pin "1") (pinfunction "1_1") (pintype "passive"))
      (node (ref "R97") (pin "1") (pinfunction "1_1") (pintype "passive"))
      (node (ref "R98") (pin "1") (pinfunction "1_1") (pintype "passive"))
      (node (ref "R99") (pin "1") (pinfunction "1_1") (pintype "passive"))
      (node (ref "TC1") (pin "1") (pinfunction "GND_1") (pintype "power_in"))
      (node (ref "TC1") (pin "10") (pinfunction "GND_10") (pintype "power_in"))
      (node (ref "TC1") (pin "13") (pinfunction "GND_13") (pintype "power_in"))
      (node (ref "TC1") (pin "17") (pinfunction "GND_17") (pintype "power_in"))
      (node (ref "TC1") (pin "18") (pinfunction "GND_18") (pintype "power_in"))
      (node (ref "TC1") (pin "21") (pinfunction "EP_21") (pintype "passive"))
      (node (ref "TC1") (pin "3") (pinfunction "GND_3") (pintype "power_in"))
      (node (ref "TC1") (pin "5") (pinfunction "GND_5") (pintype "power_in"))
      (node (ref "TC2") (pin "1") (pinfunction "GND_1") (pintype "power_in"))
      (node (ref "TC2") (pin "10") (pinfunction "GND_10") (pintype "power_in"))
      (node (ref "TC2") (pin "13") (pinfunction "GND_13") (pintype "power_in"))
      (node (ref "TC2") (pin "17") (pinfunction "GND_17") (pintype "power_in"))
      (node (ref "TC2") (pin "18") (pinfunction "GND_18") (pintype "power_in"))
      (node (ref "TC2") (pin "21") (pinfunction "EP_21") (pintype "passive"))
      (node (ref "TC2") (pin "3") (pinfunction "GND_3") (pintype "power_in"))
      (node (ref "TC2") (pin "5") (pinfunction "GND_5") (pintype "power_in"))
      (node (ref "TC3") (pin "1") (pinfunction "GND_1") (pintype "power_in"))
      (node (ref "TC3") (pin "10") (pinfunction "GND_10") (pintype "power_in"))
      (node (ref "TC3") (pin "13") (pinfunction "GND_13") (pintype "power_in"))
      (node (ref "TC3") (pin "17") (pinfunction "GND_17") (pintype "power_in"))
      (node (ref "TC3") (pin "18") (pinfunction "GND_18") (pintype "power_in"))
      (node (ref "TC3") (pin "21") (pinfunction "EP_21") (pintype "passive"))
      (node (ref "TC3") (pin "3") (pinfunction "GND_3") (pintype "power_in"))
      (node (ref "TC3") (pin "5") (pinfunction "GND_5") (pintype "power_in"))
      (node (ref "TC4") (pin "1") (pinfunction "GND_1") (pintype "power_in"))
      (node (ref "TC4") (pin "10") (pinfunction "GND_10") (pintype "power_in"))
      (node (ref "TC4") (pin "13") (pinfunction "GND_13") (pintype "power_in"))
      (node (ref "TC4") (pin "17") (pinfunction "GND_17") (pintype "power_in"))
      (node (ref "TC4") (pin "18") (pinfunction "GND_18") (pintype "power_in"))
      (node (ref "TC4") (pin "21") (pinfunction "EP_21") (pintype "passive"))
      (node (ref "TC4") (pin "3") (pinfunction "GND_3") (pintype "power_in"))
      (node (ref "TC4") (pin "5") (pinfunction "GND_5") (pintype "power_in"))
      (node (ref "TC5") (pin "1") (pinfunction "GND_1") (pintype "power_in"))
      (node (ref "TC5") (pin "10") (pinfunction "GND_10") (pintype "power_in"))
      (node (ref "TC5") (pin "13") (pinfunction "GND_13") (pintype "power_in"))
      (node (ref "TC5") (pin "17") (pinfunction "GND_17") (pintype "power_in"))
      (node (ref "TC5") (pin "18") (pinfunction "GND_18") (pintype "power_in"))
      (node (ref "TC5") (pin "21") (pinfunction "EP_21") (pintype "passive"))
      (node (ref "TC5") (pin "3") (pinfunction "GND_3") (pintype "power_in"))
      (node (ref "TC5") (pin "5") (pinfunction "GND_5") (pintype "power_in"))
      (node (ref "TC6") (pin "1") (pinfunction "GND_1") (pintype "power_in"))
      (node (ref "TC6") (pin "10") (pinfunction "GND_10") (pintype "power_in"))
      (node (ref "TC6") (pin "13") (pinfunction "GND_13") (pintype "power_in"))
      (node (ref "TC6") (pin "17") (pinfunction "GND_17") (pintype "power_in"))
      (node (ref "TC6") (pin "18") (pinfunction "GND_18") (pintype "power_in"))
      (node (ref "TC6") (pin "21") (pinfunction "EP_21") (pintype "passive"))
      (node (ref "TC6") (pin "3") (pinfunction "GND_3") (pintype "power_in"))
      (node (ref "TC6") (pin "5") (pinfunction "GND_5") (pintype "power_in"))
      (node (ref "TC7") (pin "1") (pinfunction "GND_1") (pintype "power_in"))
      (node (ref "TC7") (pin "10") (pinfunction "GND_10") (pintype "power_in"))
      (node (ref "TC7") (pin "13") (pinfunction "GND_13") (pintype "power_in"))
      (node (ref "TC7") (pin "17") (pinfunction "GND_17") (pintype "power_in"))
      (node (ref "TC7") (pin "18") (pinfunction "GND_18") (pintype "power_in"))
      (node (ref "TC7") (pin "21") (pinfunction "EP_21") (pintype "passive"))
      (node (ref "TC7") (pin "3") (pinfunction "GND_3") (pintype "power_in"))
      (node (ref "TC7") (pin "5") (pinfunction "GND_5") (pintype "power_in"))
      (node (ref "TC8") (pin "1") (pinfunction "GND_1") (pintype "power_in"))
      (node (ref "TC8") (pin "10") (pinfunction "GND_10") (pintype "power_in"))
      (node (ref "TC8") (pin "13") (pinfunction "GND_13") (pintype "power_in"))
      (node (ref "TC8") (pin "17") (pinfunction "GND_17") (pintype "power_in"))
      (node (ref "TC8") (pin "18") (pinfunction "GND_18") (pintype "power_in"))
      (node (ref "TC8") (pin "21") (pinfunction "EP_21") (pintype "passive"))
      (node (ref "TC8") (pin "3") (pinfunction "GND_3") (pintype "power_in"))
      (node (ref "TC8") (pin "5") (pinfunction "GND_5") (pintype "power_in"))
    )
    (net (code "38") (name "Net-(TC1-ADDR)") (class "Default")
      (node (ref "R48") (pin "2") (pinfunction "2_2") (pintype "passive"))
      (node (ref "R54") (pin "1") (pinfunction "1_1") (pintype "passive"))
      (node (ref "TC1") (pin "16") (pinfunction "ADDR_16") (pintype "passive"))
    )
    (net (code "39") (name "Net-(TC1-ALERT1)") (class "Default")
      (node (ref "TC1") (pin "11") (pinfunction "ALERT1_11") (pintype "passive"))
      (node (ref "TP44") (pin "1") (pinfunction "1_1") (pintype "passive"))
    )
    (net (code "40") (name "Net-(TC1-ALERT2)") (class "Default")
      (node (ref "TC1") (pin "12") (pinfunction "ALERT2_12") (pintype "passive"))
      (node (ref "TP43") (pin "1") (pinfunction "1_1") (pintype "passive"))
    )
    (net (code "41") (name "Net-(TC1-ALERT3)") (class "Default")
      (node (ref "TC1") (pin "14") (pinfunction "ALERT3_14") (pintype "passive"))
      (node (ref "TP42") (pin "1") (pinfunction "1_1") (pintype "passive"))
    )
    (net (code "42") (name "Net-(TC1-ALERT4)") (class "Default")
      (node (ref "TC1") (pin "15") (pinfunction "ALERT4_15") (pintype "passive"))
      (node (ref "TP41") (pin "1") (pinfunction "1_1") (pintype "passive"))
    )
    (net (code "43") (name "Net-(TC1-OC_ALERT)") (class "Default")
      (node (ref "TC1") (pin "9") (pinfunction "OC_ALERT_9") (pintype "passive"))
      (node (ref "TP6") (pin "1") (pinfunction "1_1") (pintype "passive"))
    )
    (net (code "44") (name "Net-(TC1-SC_ALERT)") (class "Default")
      (node (ref "TC1") (pin "7") (pinfunction "SC_ALERT_7") (pintype "passive"))
      (node (ref "TP5") (pin "1") (pinfunction "1_1") (pintype "passive"))
    )
    (net (code "45") (name "Net-(TC1-VIN+)") (class "Default")
      (node (ref "C47") (pin "1") (pinfunction "1_1") (pintype "passive"))
      (node (ref "R51") (pin "2") (pinfunction "2_2") (pintype "passive"))
      (node (ref "R59") (pin "1") (pinfunction "1_1") (pintype "passive"))
      (node (ref "R68") (pin "1") (pinfunction "1_1") (pintype "passive"))
      (node (ref "TC1") (pin "2") (pinfunction "VIN+_2") (pintype "passive"))
      (node (ref "TC1") (pin "6") (pinfunction "V_SENSE_6") (pintype "passive"))
    )
    (net (code "46") (name "Net-(TC1-VIN-)") (class "Default")
      (node (ref "C47") (pin "2") (pinfunction "2_2") (pintype "passive"))
      (node (ref "R45") (pin "2") (pinfunction "2_2") (pintype "passive"))
      (node (ref "R69") (pin "1") (pinfunction "1_1") (pintype "passive"))
      (node (ref "TC1") (pin "4") (pinfunction "VIN-_4") (pintype "passive"))
    )
    (net (code "47") (name "Net-(TC2-ADDR)") (class "Default")
      (node (ref "R46") (pin "2") (pinfunction "2_2") (pintype "passive"))
      (node (ref "R52") (pin "1") (pinfunction "1_1") (pintype "passive"))
      (node (ref "TC2") (pin "16") (pinfunction "ADDR_16") (pintype "passive"))
    )
    (net (code "48") (name "Net-(TC2-ALERT1)") (class "Default")
      (node (ref "TC2") (pin "11") (pinfunction "ALERT1_11") (pintype "passive"))
      (node (ref "TP36") (pin "1") (pinfunction "1_1") (pintype "passive"))
    )
    (net (code "49") (name "Net-(TC2-ALERT2)") (class "Default")
      (node (ref "TC2") (pin "12") (pinfunction "ALERT2_12") (pintype "passive"))
      (node (ref "TP35") (pin "1") (pinfunction "1_1") (pintype "passive"))
    )
    (net (code "50") (name "Net-(TC2-ALERT3)") (class "Default")
      (node (ref "TC2") (pin "14") (pinfunction "ALERT3_14") (pintype "passive"))
      (node (ref "TP34") (pin "1") (pinfunction "1_1") (pintype "passive"))
    )
    (net (code "51") (name "Net-(TC2-ALERT4)") (class "Default")
      (node (ref "TC2") (pin "15") (pinfunction "ALERT4_15") (pintype "passive"))
      (node (ref "TP33") (pin "1") (pinfunction "1_1") (pintype "passive"))
    )
    (net (code "52") (name "Net-(TC2-OC_ALERT)") (class "Default")
      (node (ref "TC2") (pin "9") (pinfunction "OC_ALERT_9") (pintype "passive"))
      (node (ref "TP2") (pin "1") (pinfunction "1_1") (pintype "passive"))
    )
    (net (code "53") (name "Net-(TC2-SC_ALERT)") (class "Default")
      (node (ref "TC2") (pin "7") (pinfunction "SC_ALERT_7") (pintype "passive"))
      (node (ref "TP1") (pin "1") (pinfunction "1_1") (pintype "passive"))
    )
    (net (code "54") (name "Net-(TC2-VIN+)") (class "Default")
      (node (ref "C45") (pin "1") (pinfunction "1_1") (pintype "passive"))
      (node (ref "R49") (pin "2") (pinfunction "2_2") (pintype "passive"))
      (node (ref "R55") (pin "1") (pinfunction "1_1") (pintype "passive"))
      (node (ref "R64") (pin "1") (pinfunction "1_1") (pintype "passive"))
      (node (ref "TC2") (pin "2") (pinfunction "VIN+_2") (pintype "passive"))
      (node (ref "TC2") (pin "6") (pinfunction "V_SENSE_6") (pintype "passive"))
    )
    (net (code "55") (name "Net-(TC2-VIN-)") (class "Default")
      (node (ref "C45") (pin "2") (pinfunction "2_2") (pintype "passive"))
      (node (ref "R43") (pin "2") (pinfunction "2_2") (pintype "passive"))
      (node (ref "R65") (pin "1") (pinfunction "1_1") (pintype "passive"))
      (node (ref "TC2") (pin "4") (pinfunction "VIN-_4") (pintype "passive"))
    )
    (net (code "56") (name "Net-(TC3-ADDR)") (class "Default")
      (node (ref "R47") (pin "2") (pinfunction "2_2") (pintype "passive"))
      (node (ref "R53") (pin "1") (pinfunction "1_1") (pintype "passive"))
      (node (ref "TC3") (pin "16") (pinfunction "ADDR_16") (pintype "passive"))
    )
    (net (code "57") (name "Net-(TC3-ALERT1)") (class "Default")
      (node (ref "TC3") (pin "11") (pinfunction "ALERT1_11") (pintype "passive"))
      (node (ref "TP40") (pin "1") (pinfunction "1_1") (pintype "passive"))
    )
    (net (code "58") (name "Net-(TC3-ALERT2)") (class "Default")
      (node (ref "TC3") (pin "12") (pinfunction "ALERT2_12") (pintype "passive"))
      (node (ref "TP39") (pin "1") (pinfunction "1_1") (pintype "passive"))
    )
    (net (code "59") (name "Net-(TC3-ALERT3)") (class "Default")
      (node (ref "TC3") (pin "14") (pinfunction "ALERT3_14") (pintype "passive"))
      (node (ref "TP38") (pin "1") (pinfunction "1_1") (pintype "passive"))
    )
    (net (code "60") (name "Net-(TC3-ALERT4)") (class "Default")
      (node (ref "TC3") (pin "15") (pinfunction "ALERT4_15") (pintype "passive"))
      (node (ref "TP37") (pin "1") (pinfunction "1_1") (pintype "passive"))
    )
    (net (code "61") (name "Net-(TC3-OC_ALERT)") (class "Default")
      (node (ref "TC3") (pin "9") (pinfunction "OC_ALERT_9") (pintype "passive"))
      (node (ref "TP4") (pin "1") (pinfunction "1_1") (pintype "passive"))
    )
    (net (code "62") (name "Net-(TC3-SC_ALERT)") (class "Default")
      (node (ref "TC3") (pin "7") (pinfunction "SC_ALERT_7") (pintype "passive"))
      (node (ref "TP3") (pin "1") (pinfunction "1_1") (pintype "passive"))
    )
    (net (code "63") (name "Net-(TC3-VIN+)") (class "Default")
      (node (ref "C46") (pin "1") (pinfunction "1_1") (pintype "passive"))
      (node (ref "R50") (pin "2") (pinfunction "2_2") (pintype "passive"))
      (node (ref "R56") (pin "1") (pinfunction "1_1") (pintype "passive"))
      (node (ref "R66") (pin "1") (pinfunction "1_1") (pintype "passive"))
      (node (ref "TC3") (pin "2") (pinfunction "VIN+_2") (pintype "passive"))
      (node (ref "TC3") (pin "6") (pinfunction "V_SENSE_6") (pintype "passive"))
    )
    (net (code "64") (name "Net-(TC3-VIN-)") (class "Default")
      (node (ref "C46") (pin "2") (pinfunction "2_2") (pintype "passive"))
      (node (ref "R44") (pin "2") (pinfunction "2_2") (pintype "passive"))
      (node (ref "R67") (pin "1") (pinfunction "1_1") (pintype "passive"))
      (node (ref "TC3") (pin "4") (pinfunction "VIN-_4") (pintype "passive"))
    )
    (net (code "65") (name "Net-(TC4-ADDR)") (class "Default")
      (node (ref "R75") (pin "2") (pinfunction "2_2") (pintype "passive"))
      (node (ref "R81") (pin "1") (pinfunction "1_1") (pintype "passive"))
      (node (ref "TC4") (pin "16") (pinfunction "ADDR_16") (pintype "passive"))
    )
    (net (code "66") (name "Net-(TC4-ALERT1)") (class "Default")
      (node (ref "TC4") (pin "11") (pinfunction "ALERT1_11") (pintype "passive"))
      (node (ref "TP56") (pin "1") (pinfunction "1_1") (pintype "passive"))
    )
    (net (code "67") (name "Net-(TC4-ALERT2)") (class "Default")
      (node (ref "TC4") (pin "12") (pinfunction "ALERT2_12") (pintype "passive"))
      (node (ref "TP55") (pin "1") (pinfunction "1_1") (pintype "passive"))
    )
    (net (code "68") (name "Net-(TC4-ALERT3)") (class "Default")
      (node (ref "TC4") (pin "14") (pinfunction "ALERT3_14") (pintype "passive"))
      (node (ref "TP54") (pin "1") (pinfunction "1_1") (pintype "passive"))
    )
    (net (code "69") (name "Net-(TC4-ALERT4)") (class "Default")
      (node (ref "TC4") (pin "15") (pinfunction "ALERT4_15") (pintype "passive"))
      (node (ref "TP53") (pin "1") (pinfunction "1_1") (pintype "passive"))
    )
    (net (code "70") (name "Net-(TC4-OC_ALERT)") (class "Default")
      (node (ref "TC4") (pin "9") (pinfunction "OC_ALERT_9") (pintype "passive"))
      (node (ref "TP12") (pin "1") (pinfunction "1_1") (pintype "passive"))
    )
    (net (code "71") (name "Net-(TC4-SC_ALERT)") (class "Default")
      (node (ref "TC4") (pin "7") (pinfunction "SC_ALERT_7") (pintype "passive"))
      (node (ref "TP11") (pin "1") (pinfunction "1_1") (pintype "passive"))
    )
    (net (code "72") (name "Net-(TC4-VIN+)") (class "Default")
      (node (ref "C53") (pin "1") (pinfunction "1_1") (pintype "passive"))
      (node (ref "R78") (pin "2") (pinfunction "2_2") (pintype "passive"))
      (node (ref "R86") (pin "1") (pinfunction "1_1") (pintype "passive"))
      (node (ref "R95") (pin "1") (pinfunction "1_1") (pintype "passive"))
      (node (ref "TC4") (pin "2") (pinfunction "VIN+_2") (pintype "passive"))
      (node (ref "TC4") (pin "6") (pinfunction "V_SENSE_6") (pintype "passive"))
    )
    (net (code "73") (name "Net-(TC4-VIN-)") (class "Default")
      (node (ref "C53") (pin "2") (pinfunction "2_2") (pintype "passive"))
      (node (ref "R74") (pin "2") (pinfunction "2_2") (pintype "passive"))
      (node (ref "R96") (pin "1") (pinfunction "1_1") (pintype "passive"))
      (node (ref "TC4") (pin "4") (pinfunction "VIN-_4") (pintype "passive"))
    )
    (net (code "74") (name "Net-(TC5-ADDR)") (class "Default")
      (node (ref "R72") (pin "2") (pinfunction "2_2") (pintype "passive"))
      (node (ref "R79") (pin "1") (pinfunction "1_1") (pintype "passive"))
      (node (ref "TC5") (pin "16") (pinfunction "ADDR_16") (pintype "passive"))
    )
    (net (code "75") (name "Net-(TC5-ALERT1)") (class "Default")
      (node (ref "TC5") (pin "11") (pinfunction "ALERT1_11") (pintype "passive"))
      (node (ref "TP48") (pin "1") (pinfunction "1_1") (pintype "passive"))
    )
    (net (code "76") (name "Net-(TC5-ALERT2)") (class "Default")
      (node (ref "TC5") (pin "12") (pinfunction "ALERT2_12") (pintype "passive"))
      (node (ref "TP47") (pin "1") (pinfunction "1_1") (pintype "passive"))
    )
    (net (code "77") (name "Net-(TC5-ALERT3)") (class "Default")
      (node (ref "TC5") (pin "14") (pinfunction "ALERT3_14") (pintype "passive"))
      (node (ref "TP46") (pin "1") (pinfunction "1_1") (pintype "passive"))
    )
    (net (code "78") (name "Net-(TC5-ALERT4)") (class "Default")
      (node (ref "TC5") (pin "15") (pinfunction "ALERT4_15") (pintype "passive"))
      (node (ref "TP45") (pin "1") (pinfunction "1_1") (pintype "passive"))
    )
    (net (code "79") (name "Net-(TC5-OC_ALERT)") (class "Default")
      (node (ref "TC5") (pin "9") (pinfunction "OC_ALERT_9") (pintype "passive"))
      (node (ref "TP8") (pin "1") (pinfunction "1_1") (pintype "passive"))
    )
    (net (code "80") (name "Net-(TC5-SC_ALERT)") (class "Default")
      (node (ref "TC5") (pin "7") (pinfunction "SC_ALERT_7") (pintype "passive"))
      (node (ref "TP7") (pin "1") (pinfunction "1_1") (pintype "passive"))
    )
    (net (code "81") (name "Net-(TC5-VIN+)") (class "Default")
      (node (ref "C51") (pin "1") (pinfunction "1_1") (pintype "passive"))
      (node (ref "R76") (pin "2") (pinfunction "2_2") (pintype "passive"))
      (node (ref "R82") (pin "1") (pinfunction "1_1") (pintype "passive"))
      (node (ref "R90") (pin "1") (pinfunction "1_1") (pintype "passive"))
      (node (ref "TC5") (pin "2") (pinfunction "VIN+_2") (pintype "passive"))
      (node (ref "TC5") (pin "6") (pinfunction "V_SENSE_6") (pintype "passive"))
    )
    (net (code "82") (name "Net-(TC5-VIN-)") (class "Default")
      (node (ref "C51") (pin "2") (pinfunction "2_2") (pintype "passive"))
      (node (ref "R70") (pin "2") (pinfunction "2_2") (pintype "passive"))
      (node (ref "R91") (pin "1") (pinfunction "1_1") (pintype "passive"))
      (node (ref "TC5") (pin "4") (pinfunction "VIN-_4") (pintype "passive"))
    )
    (net (code "83") (name "Net-(TC6-ADDR)") (class "Default")
      (node (ref "R73") (pin "2") (pinfunction "2_2") (pintype "passive"))
      (node (ref "R80") (pin "1") (pinfunction "1_1") (pintype "passive"))
      (node (ref "TC6") (pin "16") (pinfunction "ADDR_16") (pintype "passive"))
    )
    (net (code "84") (name "Net-(TC6-ALERT1)") (class "Default")
      (node (ref "TC6") (pin "11") (pinfunction "ALERT1_11") (pintype "passive"))
      (node (ref "TP52") (pin "1") (pinfunction "1_1") (pintype "passive"))
    )
    (net (code "85") (name "Net-(TC6-ALERT2)") (class "Default")
      (node (ref "TC6") (pin "12") (pinfunction "ALERT2_12") (pintype "passive"))
      (node (ref "TP51") (pin "1") (pinfunction "1_1") (pintype "passive"))
    )
    (net (code "86") (name "Net-(TC6-ALERT3)") (class "Default")
      (node (ref "TC6") (pin "14") (pinfunction "ALERT3_14") (pintype "passive"))
      (node (ref "TP50") (pin "1") (pinfunction "1_1") (pintype "passive"))
    )
    (net (code "87") (name "Net-(TC6-ALERT4)") (class "Default")
      (node (ref "TC6") (pin "15") (pinfunction "ALERT4_15") (pintype "passive"))
      (node (ref "TP49") (pin "1") (pinfunction "1_1") (pintype "passive"))
    )
    (net (code "88") (name "Net-(TC6-OC_ALERT)") (class "Default")
      (node (ref "TC6") (pin "9") (pinfunction "OC_ALERT_9") (pintype "passive"))
      (node (ref "TP10") (pin "1") (pinfunction "1_1") (pintype "passive"))
    )
    (net (code "89") (name "Net-(TC6-SC_ALERT)") (class "Default")
      (node (ref "TC6") (pin "7") (pinfunction "SC_ALERT_7") (pintype "passive"))
      (node (ref "TP9") (pin "1") (pinfunction "1_1") (pintype "passive"))
    )
    (net (code "90") (name "Net-(TC6-VIN+)") (class "Default")
      (node (ref "C52") (pin "1") (pinfunction "1_1") (pintype "passive"))
      (node (ref "R77") (pin "2") (pinfunction "2_2") (pintype "passive"))
      (node (ref "R83") (pin "1") (pinfunction "1_1") (pintype "passive"))
      (node (ref "R92") (pin "1") (pinfunction "1_1") (pintype "passive"))
      (node (ref "TC6") (pin "2") (pinfunction "VIN+_2") (pintype "passive"))
      (node (ref "TC6") (pin "6") (pinfunction "V_SENSE_6") (pintype "passive"))
    )
    (net (code "91") (name "Net-(TC6-VIN-)") (class "Default")
      (node (ref "C52") (pin "2") (pinfunction "2_2") (pintype "passive"))
      (node (ref "R71") (pin "2") (pinfunction "2_2") (pintype "passive"))
      (node (ref "R93") (pin "1") (pinfunction "1_1") (pintype "passive"))
      (node (ref "TC6") (pin "4") (pinfunction "VIN-_4") (pintype "passive"))
    )
    (net (code "92") (name "Net-(TC7-ADDR)") (class "Default")
      (node (ref "R103") (pin "1") (pinfunction "1_1") (pintype "passive"))
      (node (ref "R99") (pin "2") (pinfunction "2_2") (pintype "passive"))
      (node (ref "TC7") (pin "16") (pinfunction "ADDR_16") (pintype "passive"))
    )
    (net (code "93") (name "Net-(TC7-ALERT1)") (class "Default")
      (node (ref "TC7") (pin "11") (pinfunction "ALERT1_11") (pintype "passive"))
      (node (ref "TP60") (pin "1") (pinfunction "1_1") (pintype "passive"))
    )
    (net (code "94") (name "Net-(TC7-ALERT2)") (class "Default")
      (node (ref "TC7") (pin "12") (pinfunction "ALERT2_12") (pintype "passive"))
      (node (ref "TP59") (pin "1") (pinfunction "1_1") (pintype "passive"))
    )
    (net (code "95") (name "Net-(TC7-ALERT3)") (class "Default")
      (node (ref "TC7") (pin "14") (pinfunction "ALERT3_14") (pintype "passive"))
      (node (ref "TP58") (pin "1") (pinfunction "1_1") (pintype "passive"))
    )
    (net (code "96") (name "Net-(TC7-ALERT4)") (class "Default")
      (node (ref "TC7") (pin "15") (pinfunction "ALERT4_15") (pintype "passive"))
      (node (ref "TP57") (pin "1") (pinfunction "1_1") (pintype "passive"))
    )
    (net (code "97") (name "Net-(TC7-OC_ALERT)") (class "Default")
      (node (ref "TC7") (pin "9") (pinfunction "OC_ALERT_9") (pintype "passive"))
      (node (ref "TP14") (pin "1") (pinfunction "1_1") (pintype "passive"))
    )
    (net (code "98") (name "Net-(TC7-SC_ALERT)") (class "Default")
      (node (ref "TC7") (pin "7") (pinfunction "SC_ALERT_7") (pintype "passive"))
      (node (ref "TP13") (pin "1") (pinfunction "1_1") (pintype "passive"))
    )
    (net (code "99") (name "Net-(TC7-VIN+)") (class "Default")
      (node (ref "C56") (pin "1") (pinfunction "1_1") (pintype "passive"))
      (node (ref "R101") (pin "2") (pinfunction "2_2") (pintype "passive"))
      (node (ref "R105") (pin "1") (pinfunction "1_1") (pintype "passive"))
      (node (ref "R111") (pin "1") (pinfunction "1_1") (pintype "passive"))
      (node (ref "TC7") (pin "2") (pinfunction "VIN+_2") (pintype "passive"))
      (node (ref "TC7") (pin "6") (pinfunction "V_SENSE_6") (pintype "passive"))
    )
    (net (code "100") (name "Net-(TC7-VIN-)") (class "Default")
      (node (ref "C56") (pin "2") (pinfunction "2_2") (pintype "passive"))
      (node (ref "R112") (pin "1") (pinfunction "1_1") (pintype "passive"))
      (node (ref "R97") (pin "2") (pinfunction "2_2") (pintype "passive"))
      (node (ref "TC7") (pin "4") (pinfunction "VIN-_4") (pintype "passive"))
    )
    (net (code "101") (name "Net-(TC8-ADDR)") (class "Default")
      (node (ref "R100") (pin "2") (pinfunction "2_2") (pintype "passive"))
      (node (ref "R104") (pin "1") (pinfunction "1_1") (pintype "passive"))
      (node (ref "TC8") (pin "16") (pinfunction "ADDR_16") (pintype "passive"))
    )
    (net (code "102") (name "Net-(TC8-ALERT1)") (class "Default")
      (node (ref "TC8") (pin "11") (pinfunction "ALERT1_11") (pintype "passive"))
      (node (ref "TP64") (pin "1") (pinfunction "1_1") (pintype "passive"))
    )
    (net (code "103") (name "Net-(TC8-ALERT2)") (class "Default")
      (node (ref "TC8") (pin "12") (pinfunction "ALERT2_12") (pintype "passive"))
      (node (ref "TP63") (pin "1") (pinfunction "1_1") (pintype "passive"))
    )
    (net (code "104") (name "Net-(TC8-ALERT3)") (class "Default")
      (node (ref "TC8") (pin "14") (pinfunction "ALERT3_14") (pintype "passive"))
      (node (ref "TP62") (pin "1") (pinfunction "1_1") (pintype "passive"))
    )
    (net (code "105") (name "Net-(TC8-ALERT4)") (class "Default")
      (node (ref "TC8") (pin "15") (pinfunction "ALERT4_15") (pintype "passive"))
      (node (ref "TP61") (pin "1") (pinfunction "1_1") (pintype "passive"))
    )
    (net (code "106") (name "Net-(TC8-OC_ALERT)") (class "Default")
      (node (ref "TC8") (pin "9") (pinfunction "OC_ALERT_9") (pintype "passive"))
      (node (ref "TP16") (pin "1") (pinfunction "1_1") (pintype "passive"))
    )
    (net (code "107") (name "Net-(TC8-SC_ALERT)") (class "Default")
      (node (ref "TC8") (pin "7") (pinfunction "SC_ALERT_7") (pintype "passive"))
      (node (ref "TP15") (pin "1") (pinfunction "1_1") (pintype "passive"))
    )
    (net (code "108") (name "Net-(TC8-VIN+)") (class "Default")
      (node (ref "C57") (pin "1") (pinfunction "1_1") (pintype "passive"))
      (node (ref "R102") (pin "2") (pinfunction "2_2") (pintype "passive"))
      (node (ref "R106") (pin "1") (pinfunction "1_1") (pintype "passive"))
      (node (ref "R113") (pin "1") (pinfunction "1_1") (pintype "passive"))
      (node (ref "TC8") (pin "2") (pinfunction "VIN+_2") (pintype "passive"))
      (node (ref "TC8") (pin "6") (pinfunction "V_SENSE_6") (pintype "passive"))
    )
    (net (code "109") (name "Net-(TC8-VIN-)") (class "Default")
      (node (ref "C57") (pin "2") (pinfunction "2_2") (pintype "passive"))
      (node (ref "R114") (pin "1") (pinfunction "1_1") (pintype "passive"))
      (node (ref "R98") (pin "2") (pinfunction "2_2") (pintype "passive"))
      (node (ref "TC8") (pin "4") (pinfunction "VIN-_4") (pintype "passive"))
    )
    (net (code "110") (name "PICO_ADA_3V3") (class "Default")
      (node (ref "C42") (pin "1") (pinfunction "1_1") (pintype "passive"))
      (node (ref "C43") (pin "1") (pinfunction "1_1") (pintype "passive"))
      (node (ref "C44") (pin "1") (pinfunction "1_1") (pintype "passive"))
      (node (ref "C48") (pin "1") (pinfunction "1_1") (pintype "passive"))
      (node (ref "C49") (pin "1") (pinfunction "1_1") (pintype "passive"))
      (node (ref "C50") (pin "1") (pinfunction "1_1") (pintype "passive"))
      (node (ref "C54") (pin "1") (pinfunction "1_1") (pintype "passive"))
      (node (ref "C55") (pin "1") (pinfunction "1_1") (pintype "passive"))
      (node (ref "R103") (pin "2") (pinfunction "2_2") (pintype "passive"))
      (node (ref "R104") (pin "2") (pinfunction "2_2") (pintype "passive"))
      (node (ref "R105") (pin "2") (pinfunction "2_2") (pintype "passive"))
      (node (ref "R106") (pin "2") (pinfunction "2_2") (pintype "passive"))
      (node (ref "R107") (pin "2") (pinfunction "2_2") (pintype "passive"))
      (node (ref "R108") (pin "2") (pinfunction "2_2") (pintype "passive"))
      (node (ref "R109") (pin "2") (pinfunction "2_2") (pintype "passive"))
      (node (ref "R110") (pin "2") (pinfunction "2_2") (pintype "passive"))
      (node (ref "R52") (pin "2") (pinfunction "2_2") (pintype "passive"))
      (node (ref "R53") (pin "2") (pinfunction "2_2") (pintype "passive"))
      (node (ref "R54") (pin "2") (pinfunction "2_2") (pintype "passive"))
      (node (ref "R55") (pin "2") (pinfunction "2_2") (pintype "passive"))
      (node (ref "R56") (pin "2") (pinfunction "2_2") (pintype "passive"))
      (node (ref "R57") (pin "2") (pinfunction "2_2") (pintype "passive"))
      (node (ref "R58") (pin "2") (pinfunction "2_2") (pintype "passive"))
      (node (ref "R59") (pin "2") (pinfunction "2_2") (pintype "passive"))
      (node (ref "R60") (pin "2") (pinfunction "2_2") (pintype "passive"))
      (node (ref "R61") (pin "2") (pinfunction "2_2") (pintype "passive"))
      (node (ref "R62") (pin "2") (pinfunction "2_2") (pintype "passive"))
      (node (ref "R63") (pin "2") (pinfunction "2_2") (pintype "passive"))
      (node (ref "R79") (pin "2") (pinfunction "2_2") (pintype "passive"))
      (node (ref "R80") (pin "2") (pinfunction "2_2") (pintype "passive"))
      (node (ref "R81") (pin "2") (pinfunction "2_2") (pintype "passive"))
      (node (ref "R82") (pin "2") (pinfunction "2_2") (pintype "passive"))
      (node (ref "R83") (pin "2") (pinfunction "2_2") (pintype "passive"))
      (node (ref "R84") (pin "2") (pinfunction "2_2") (pintype "passive"))
      (node (ref "R85") (pin "2") (pinfunction "2_2") (pintype "passive"))
      (node (ref "R86") (pin "2") (pinfunction "2_2") (pintype "passive"))
      (node (ref "R87") (pin "2") (pinfunction "2_2") (pintype "passive"))
      (node (ref "R88") (pin "2") (pinfunction "2_2") (pintype "passive"))
      (node (ref "R89") (pin "2") (pinfunction "2_2") (pintype "passive"))
      (node (ref "R94") (pin "2") (pinfunction "2_2") (pintype "passive"))
      (node (ref "TC1") (pin "8") (pinfunction "VDD_8") (pintype "passive"))
      (node (ref "TC2") (pin "8") (pinfunction "VDD_8") (pintype "passive"))
      (node (ref "TC3") (pin "8") (pinfunction "VDD_8") (pintype "passive"))
      (node (ref "TC4") (pin "8") (pinfunction "VDD_8") (pintype "passive"))
      (node (ref "TC5") (pin "8") (pinfunction "VDD_8") (pintype "passive"))
      (node (ref "TC6") (pin "8") (pinfunction "VDD_8") (pintype "passive"))
      (node (ref "TC7") (pin "8") (pinfunction "VDD_8") (pintype "passive"))
      (node (ref "TC8") (pin "8") (pinfunction "VDD_8") (pintype "passive"))
    )
  )
)
